# sha2017_rev1_0_1.net
KiCad netlist of a schematic drawn in EAGLE
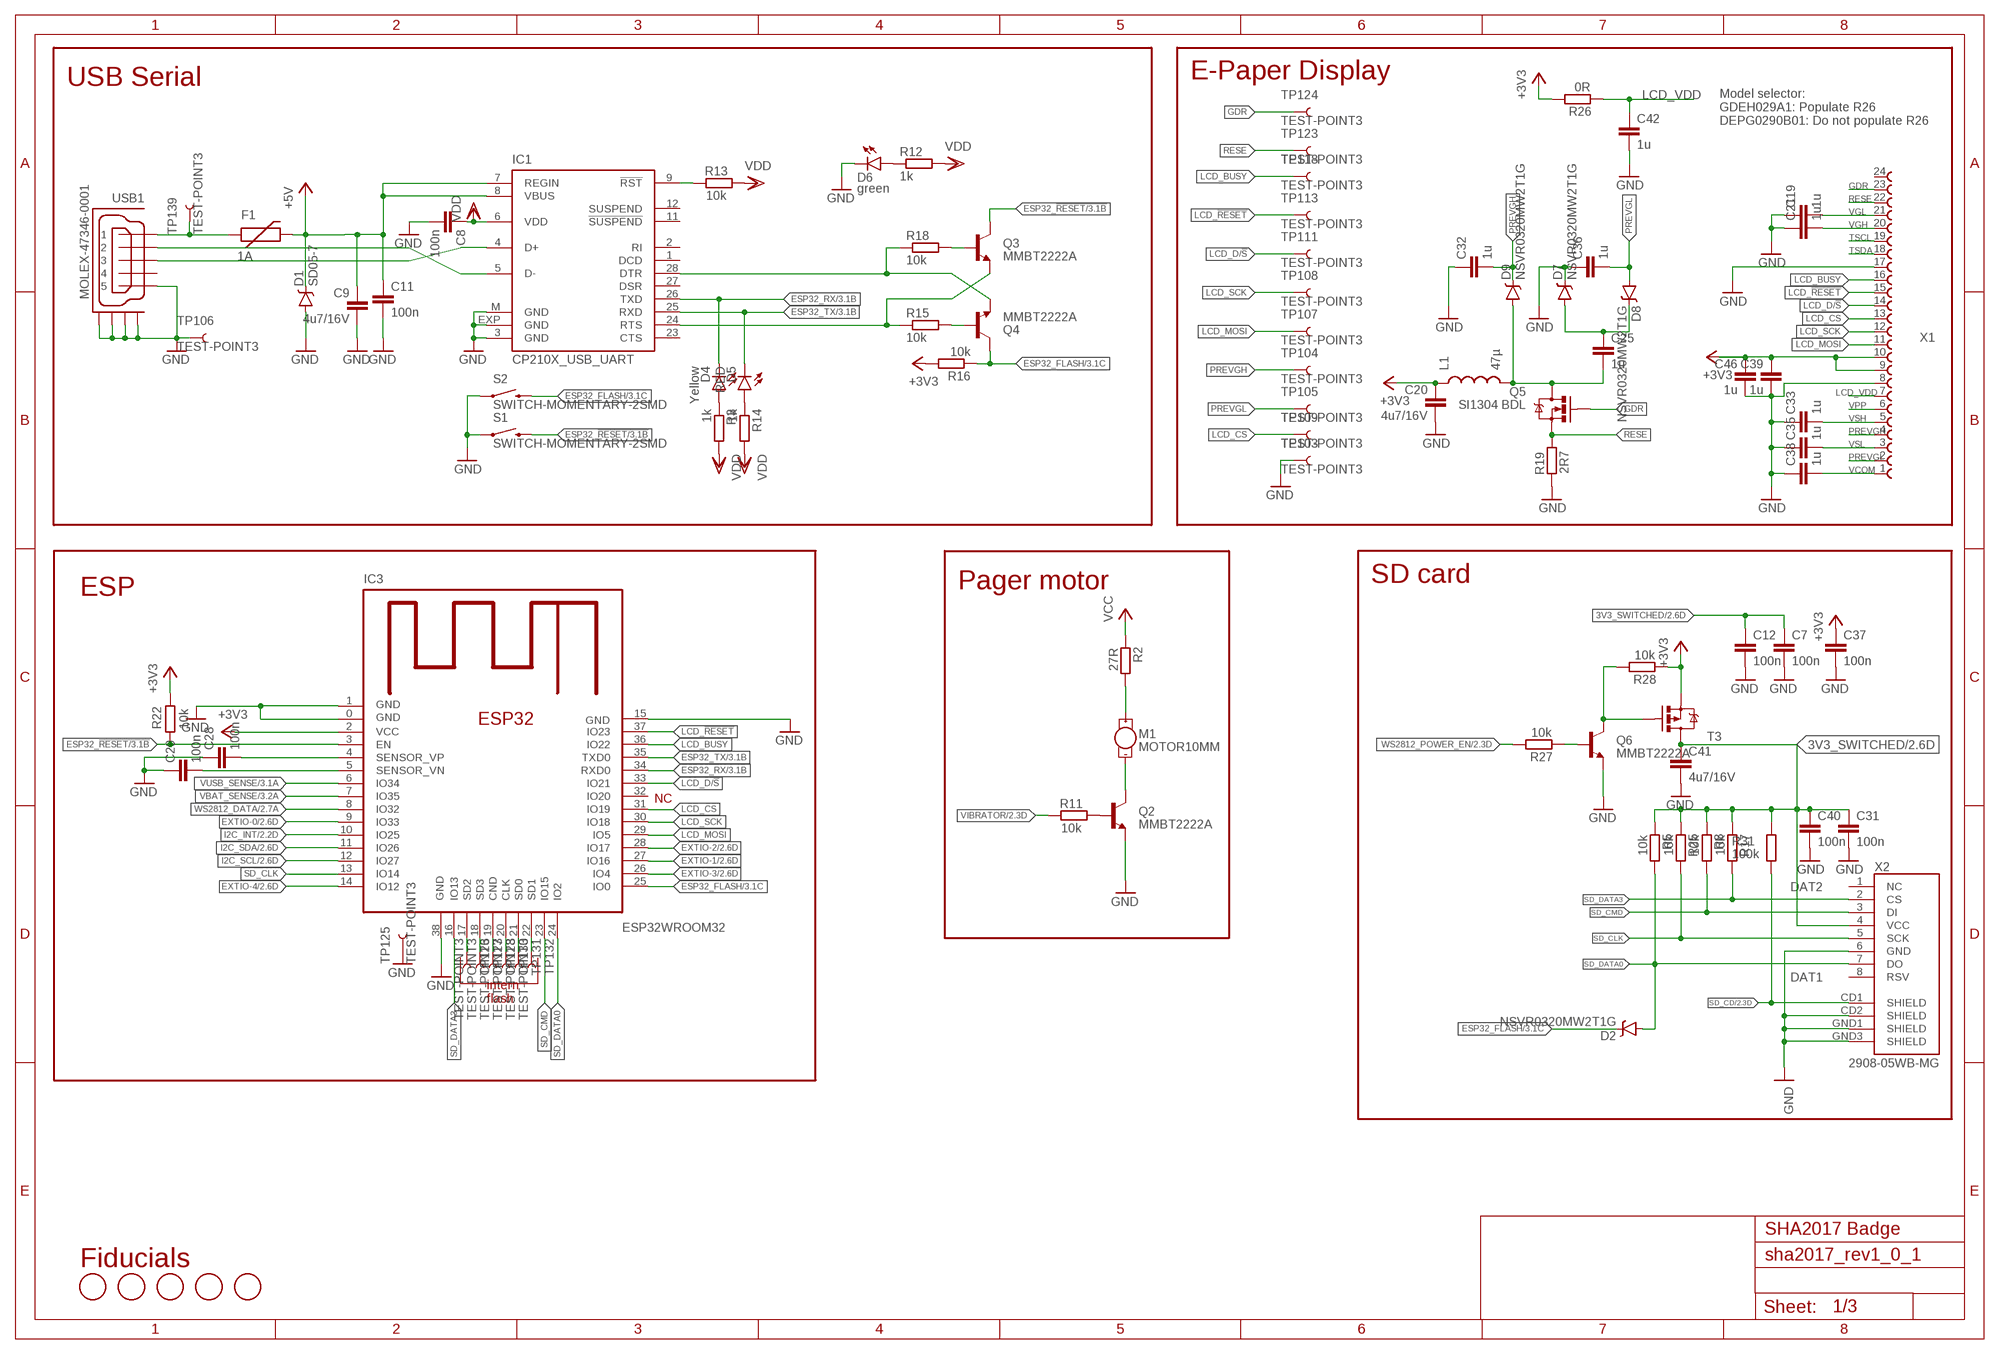
[diagram p0: schematic, sheet 1]
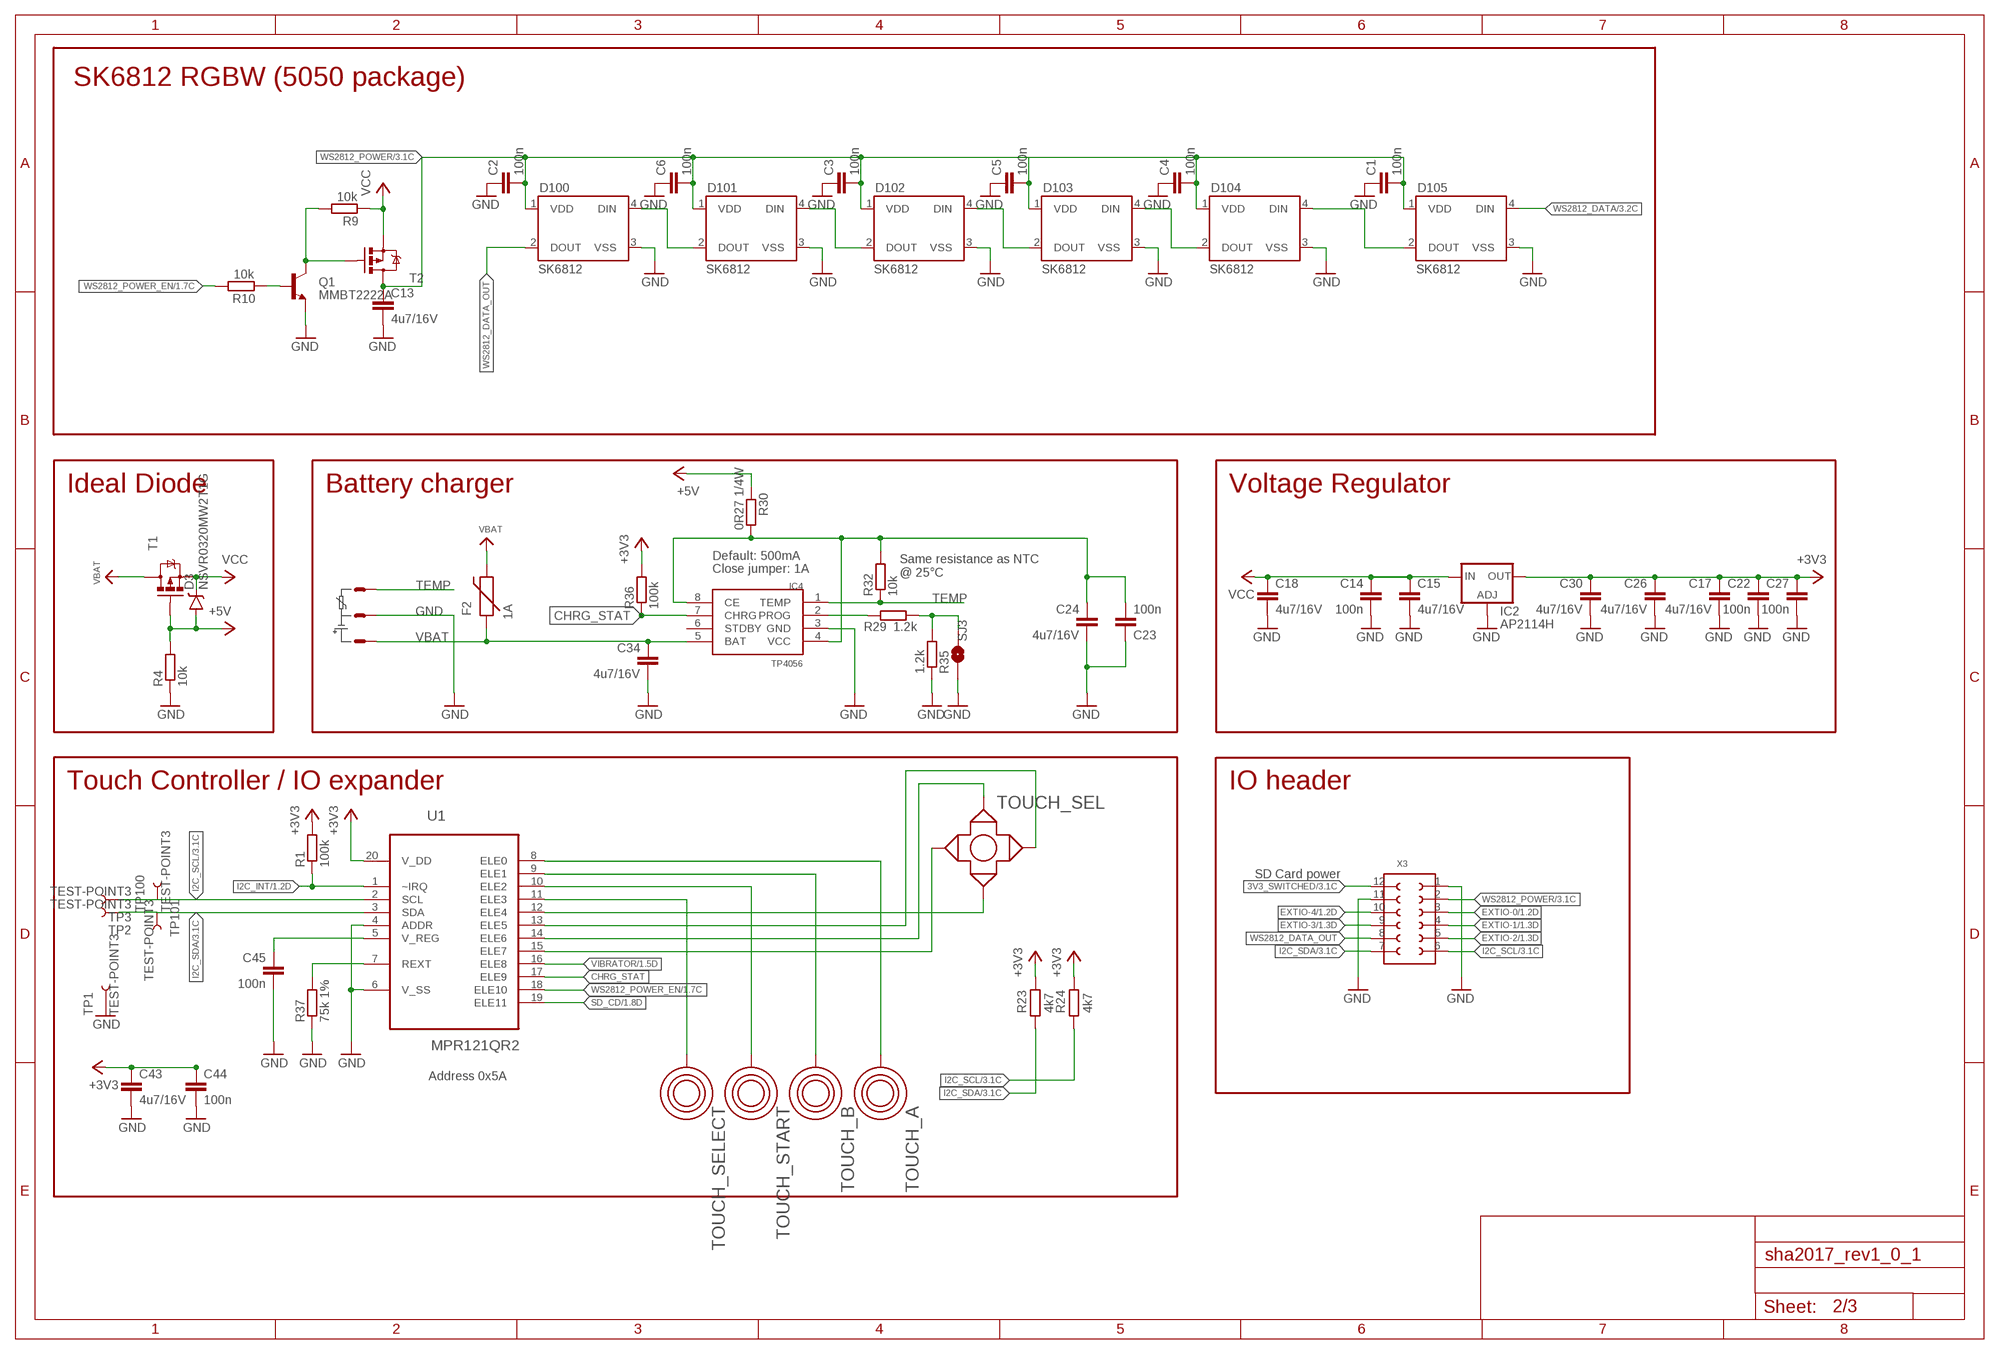
[diagram p1: schematic, sheet 2]
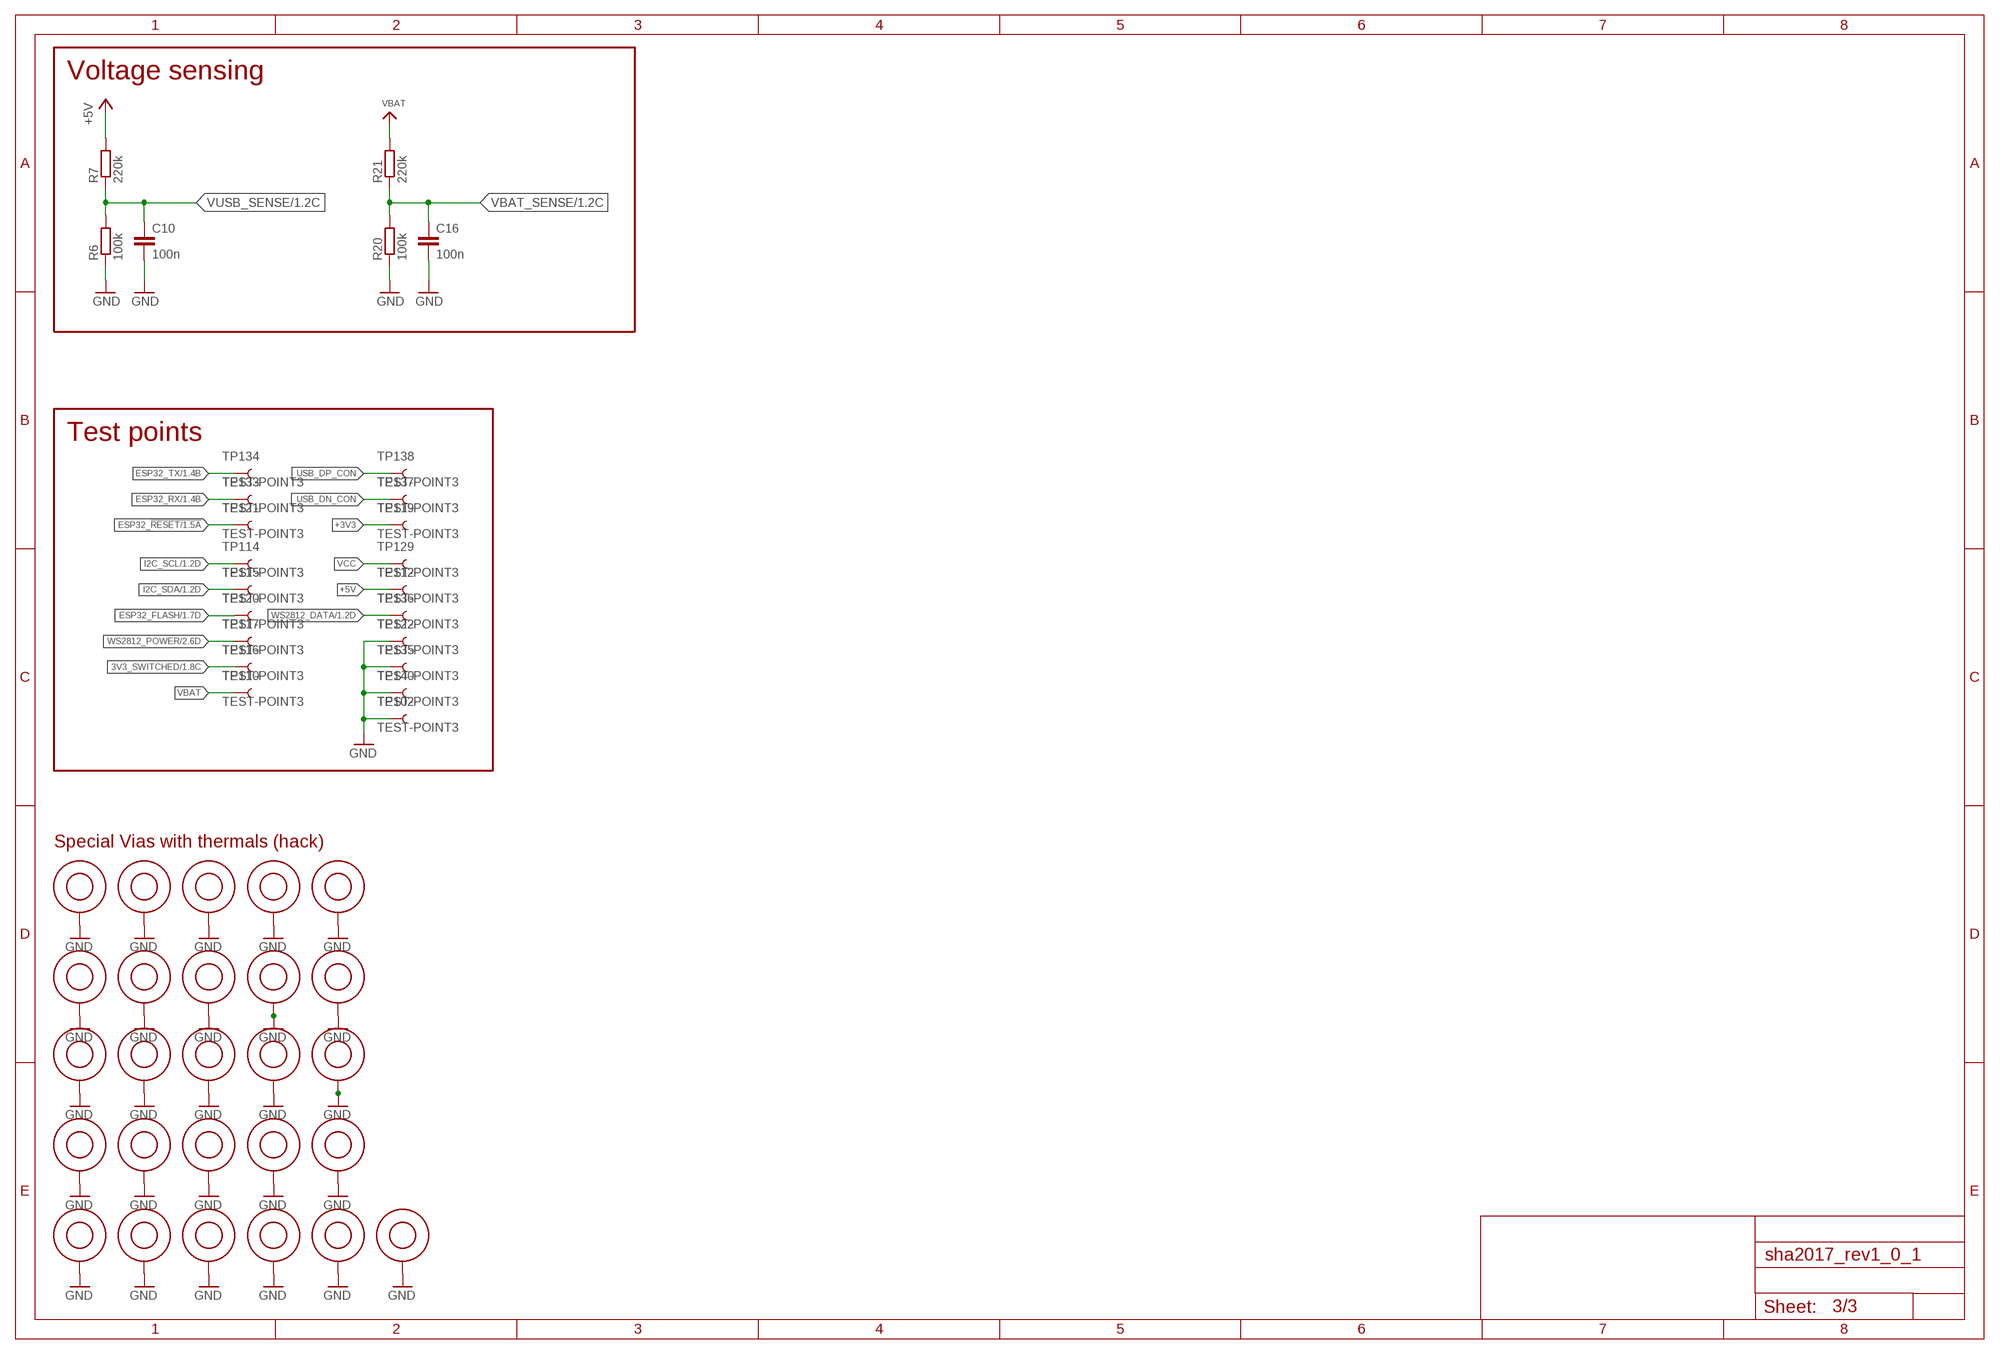
[diagram p2: schematic, sheet 3]

(export (version "E")
  (design (tool "Eeschema 10.0.6"))
  (components
    (comp (ref "C1")
      (value "100n")
      (footprint "eagle-import:C0603-DASHES")
      (fields (field (name "PARTNO") "GRM188R71H104KA93D"))
      (libsource (lib "eagle-import") (part "C0603-DASHES"))
    )
    (comp (ref "C2")
      (value "100n")
      (footprint "eagle-import:C0603-DASHES")
      (fields (field (name "PARTNO") "GRM188R71H104KA93D"))
      (libsource (lib "eagle-import") (part "C0603-DASHES"))
    )
    (comp (ref "C3")
      (value "100n")
      (footprint "eagle-import:C0603-DASHES")
      (fields (field (name "PARTNO") "GRM188R71H104KA93D"))
      (libsource (lib "eagle-import") (part "C0603-DASHES"))
    )
    (comp (ref "C4")
      (value "100n")
      (footprint "eagle-import:C0603-DASHES")
      (fields (field (name "PARTNO") "GRM188R71H104KA93D"))
      (libsource (lib "eagle-import") (part "C0603-DASHES"))
    )
    (comp (ref "C5")
      (value "100n")
      (footprint "eagle-import:C0603-DASHES")
      (fields (field (name "PARTNO") "GRM188R71H104KA93D"))
      (libsource (lib "eagle-import") (part "C0603-DASHES"))
    )
    (comp (ref "C6")
      (value "100n")
      (footprint "eagle-import:C0603-DASHES")
      (fields (field (name "PARTNO") "GRM188R71H104KA93D"))
      (libsource (lib "eagle-import") (part "C0603-DASHES"))
    )
    (comp (ref "C13")
      (value "4u7/16V")
      (footprint "eagle-import:C0805")
      (fields (field (name "PARTNO") "GRM21BR61C475KA88K"))
      (libsource (lib "eagle-import") (part "C-EUC0805"))
    )
    (comp (ref "C14")
      (value "100n")
      (footprint "eagle-import:C0603-DASHES")
      (fields (field (name "PARTNO") "GRM188R71H104KA93D"))
      (libsource (lib "eagle-import") (part "C0603-DASHES"))
    )
    (comp (ref "C15")
      (value "4u7/16V")
      (footprint "eagle-import:C0805")
      (fields (field (name "PARTNO") "GRM21BR61C475KA88K"))
      (libsource (lib "eagle-import") (part "C-EUC0805"))
    )
    (comp (ref "C17")
      (value "4u7/16V")
      (footprint "eagle-import:C0805")
      (fields (field (name "PARTNO") "GRM21BR61C475KA88K"))
      (libsource (lib "eagle-import") (part "C-EUC0805"))
    )
    (comp (ref "C18")
      (value "4u7/16V")
      (footprint "eagle-import:C0805")
      (fields (field (name "PARTNO") "GRM21BR61C475KA88K"))
      (libsource (lib "eagle-import") (part "C-EUC0805"))
    )
    (comp (ref "C22")
      (value "100n")
      (footprint "eagle-import:C0603-DASHES")
      (fields (field (name "PARTNO") "GRM188R71H104KA93D"))
      (libsource (lib "eagle-import") (part "C0603-DASHES"))
    )
    (comp (ref "C23")
      (value "100n")
      (footprint "eagle-import:C0603-DASHES")
      (fields (field (name "PARTNO") "GRM188R71H104KA93D"))
      (libsource (lib "eagle-import") (part "C0603-DASHES"))
    )
    (comp (ref "C24")
      (value "4u7/16V")
      (footprint "eagle-import:C0805")
      (fields (field (name "PARTNO") "GRM21BR61C475KA88K"))
      (libsource (lib "eagle-import") (part "C-EUC0805"))
    )
    (comp (ref "C26")
      (value "4u7/16V")
      (footprint "eagle-import:C0805")
      (fields (field (name "PARTNO") "GRM21BR61C475KA88K"))
      (libsource (lib "eagle-import") (part "C-EUC0805"))
    )
    (comp (ref "C27")
      (value "100n")
      (footprint "eagle-import:C0603-DASHES")
      (fields (field (name "PARTNO") "GRM188R71H104KA93D"))
      (libsource (lib "eagle-import") (part "C0603-DASHES"))
    )
    (comp (ref "C30")
      (value "4u7/16V")
      (footprint "eagle-import:C0805")
      (fields (field (name "PARTNO") "GRM21BR61C475KA88K"))
      (libsource (lib "eagle-import") (part "C-EUC0805"))
    )
    (comp (ref "C34")
      (value "4u7/16V")
      (footprint "eagle-import:C0805")
      (fields (field (name "PARTNO") "GRM21BR61C475KA88K"))
      (libsource (lib "eagle-import") (part "C-EUC0805"))
    )
    (comp (ref "C43")
      (value "4u7/16V")
      (footprint "eagle-import:C0805")
      (fields (field (name "PARTNO") "GRM21BR61C475KA88K"))
      (libsource (lib "eagle-import") (part "C-EUC0805"))
    )
    (comp (ref "C44")
      (value "100n")
      (footprint "eagle-import:C0603-DASHES")
      (fields (field (name "PARTNO") "GRM188R71H104KA93D"))
      (libsource (lib "eagle-import") (part "C0603-DASHES"))
    )
    (comp (ref "C45")
      (value "100n")
      (footprint "eagle-import:C0603-DASHES")
      (fields (field (name "PARTNO") "GRM188R71H104KA93D"))
      (libsource (lib "eagle-import") (part "C0603-DASHES"))
    )
    (comp (ref "D3")
      (value "NSVR0320MW2T1G")
      (footprint "eagle-import:SOD-323")
      (fields (field (name "PARTNO") "BAT20JFILM"))
      (libsource (lib "eagle-import") (part "BAT20JFILM"))
    )
    (comp (ref "D100")
      (value "SK6812")
      (footprint "eagle-import:WS2812B")
      (libsource (lib "eagle-import") (part "WS2812B"))
    )
    (comp (ref "D101")
      (value "SK6812")
      (footprint "eagle-import:WS2812B")
      (libsource (lib "eagle-import") (part "WS2812B"))
    )
    (comp (ref "D102")
      (value "SK6812")
      (footprint "eagle-import:WS2812B")
      (libsource (lib "eagle-import") (part "WS2812B"))
    )
    (comp (ref "D103")
      (value "SK6812")
      (footprint "eagle-import:WS2812B")
      (libsource (lib "eagle-import") (part "WS2812B"))
    )
    (comp (ref "D104")
      (value "SK6812")
      (footprint "eagle-import:WS2812B")
      (libsource (lib "eagle-import") (part "WS2812B"))
    )
    (comp (ref "D105")
      (value "SK6812")
      (footprint "eagle-import:WS2812B")
      (libsource (lib "eagle-import") (part "WS2812B"))
    )
    (comp (ref "F2")
      (value "1A")
      (footprint "eagle-import:PTC-1206")
      (libsource (lib "eagle-import") (part "PTCSMD"))
    )
    (comp (ref "IC2")
      (value "AP2114H")
      (footprint "eagle-import:SOT223")
      (fields (field (name "PARTNO") "AP7215-33YG-13"))
      (libsource (lib "eagle-import") (part "LD117A?S33TR"))
    )
    (comp (ref "IC4")
      (value "TP4056")
      (footprint "eagle-import:SOP-8")
      (libsource (lib "eagle-import") (part "TP4056"))
    )
    (comp (ref "Q1")
      (value "MMBT2222A")
      (footprint "eagle-import:SOT23-3")
      (fields (field (name "PARTNO") "BC817-25,215"))
      (libsource (lib "eagle-import") (part "TRANSISTOR_NPNMMBT2222A"))
    )
    (comp (ref "R1")
      (value "100k")
      (footprint "eagle-import:R0603-DASHES")
      (fields (field (name "PARTNO") "ERJ-3GEYJ104V"))
      (libsource (lib "eagle-import") (part "sha2017_rev0_1_0_dev_R0603-DASHES"))
    )
    (comp (ref "R4")
      (value "10k")
      (footprint "eagle-import:R0603-DASHES")
      (fields (field (name "PARTNO") "ERJ-3GEYJ103V"))
      (libsource (lib "eagle-import") (part "sha2017_rev0_1_0_dev_R0603-DASHES"))
    )
    (comp (ref "R9")
      (value "10k")
      (footprint "eagle-import:R0603-DASHES")
      (fields (field (name "PARTNO") "ERJ-3GEYJ103V"))
      (libsource (lib "eagle-import") (part "R0603-DASHES"))
    )
    (comp (ref "R10")
      (value "10k")
      (footprint "eagle-import:R0603-DASHES")
      (fields (field (name "PARTNO") "ERJ-3GEYJ103V"))
      (libsource (lib "eagle-import") (part "R0603-DASHES"))
    )
    (comp (ref "R23")
      (value "4k7")
      (footprint "eagle-import:R0603-DASHES")
      (fields (field (name "PARTNO") "ERJ-3GEYJ103V"))
      (libsource (lib "eagle-import") (part "sha2017_rev0_1_0_dev_R0603-DASHES"))
    )
    (comp (ref "R24")
      (value "4k7")
      (footprint "eagle-import:R0603-DASHES")
      (fields (field (name "PARTNO") "ERJ-3GEYJ103V"))
      (libsource (lib "eagle-import") (part "sha2017_rev0_1_0_dev_R0603-DASHES"))
    )
    (comp (ref "R29")
      (value "1.2k")
      (footprint "eagle-import:R0603-DASHES")
      (fields (field (name "PARTNO") "ERJ-3GEYJ222V"))
      (libsource (lib "eagle-import") (part "sha2017_rev0_1_0_dev_R0603-DASHES"))
    )
    (comp (ref "R30")
      (value "0R27 1/4W")
      (footprint "eagle-import:R1206")
      (fields (field (name "PARTNO") "ERJ-3GEYJ154V"))
      (libsource (lib "eagle-import") (part "R-EU_R1206"))
    )
    (comp (ref "R32")
      (value "10k")
      (footprint "eagle-import:R0603-DASHES")
      (fields (field (name "PARTNO") "ERJ-3GEYJ154V"))
      (libsource (lib "eagle-import") (part "sha2017_rev0_1_0_dev_R0603-DASHES"))
    )
    (comp (ref "R35")
      (value "1.2k")
      (footprint "eagle-import:R0603-DASHES")
      (fields (field (name "PARTNO") "ERJ-3GEYJ222V"))
      (libsource (lib "eagle-import") (part "sha2017_rev0_1_0_dev_R0603-DASHES"))
    )
    (comp (ref "R36")
      (value "100k")
      (footprint "eagle-import:R0603-DASHES")
      (fields (field (name "PARTNO") "ERJ-3GEYJ104V"))
      (libsource (lib "eagle-import") (part "sha2017_rev0_1_0_dev_R0603-DASHES"))
    )
    (comp (ref "R37")
      (value "75k 1%")
      (footprint "eagle-import:R0603-DASHES")
      (fields (field (name "PARTNO") "ERJ-3GEYJ104V"))
      (libsource (lib "eagle-import") (part "sha2017_rev0_1_0_dev_R0603-DASHES"))
    )
    (comp (ref "SJ3")
      (value "JUMPER-PAD-2-NOYES_SILK")
      (footprint "eagle-import:PAD-JUMPER-2-NO_YES_SILK")
      (fields (field (name "PARTNO") "NAP"))
      (libsource (lib "eagle-import") (part "JUMPER-PAD-2-NOYES_SILK"))
    )
    (comp (ref "T1")
      (value "MOSFET-PCHANNEL")
      (footprint "eagle-import:SOT23-3")
      (libsource (lib "eagle-import") (part "MOSFET-PCHANNEL"))
    )
    (comp (ref "T2")
      (value "MOSFET-PCHANNEL")
      (footprint "eagle-import:SOT23-3")
      (libsource (lib "eagle-import") (part "MOSFET-PCHANNEL"))
    )
    (comp (ref "TOUCH_A")
      (value "TOUCHROUND")
      (footprint "eagle-import:TOUCH_BUTTON")
      (fields (field (name "PARTNO") "NAP"))
      (libsource (lib "eagle-import") (part "TOUCHROUND"))
    )
    (comp (ref "TOUCH_B")
      (value "TOUCHROUND")
      (footprint "eagle-import:TOUCH_BUTTON")
      (fields (field (name "PARTNO") "NAP"))
      (libsource (lib "eagle-import") (part "TOUCHROUND"))
    )
    (comp (ref "TOUCH_SEL")
      (value "TOUCH_CROSS")
      (footprint "eagle-import:TOUCH_CROSS")
      (fields (field (name "PARTNO") "NAP"))
      (libsource (lib "eagle-import") (part "TOUCH_CROSS"))
    )
    (comp (ref "TOUCH_SELECT")
      (value "TOUCHSELECT")
      (footprint "eagle-import:TOUCH_SELECT")
      (libsource (lib "eagle-import") (part "TOUCHSELECT"))
    )
    (comp (ref "TOUCH_START")
      (value "TOUCHSELECT")
      (footprint "eagle-import:TOUCH_SELECT")
      (libsource (lib "eagle-import") (part "TOUCHSELECT"))
    )
    (comp (ref "TP1")
      (value "TEST-POINT3")
      (footprint "eagle-import:PAD.03X.03")
      (fields (field (name "PARTNO") "NAP"))
      (libsource (lib "eagle-import") (part "TEST-POINT3"))
    )
    (comp (ref "TP2")
      (value "TEST-POINT3")
      (footprint "eagle-import:PAD.03X.03")
      (fields (field (name "PARTNO") "NAP"))
      (libsource (lib "eagle-import") (part "TEST-POINT3"))
    )
    (comp (ref "TP3")
      (value "TEST-POINT3")
      (footprint "eagle-import:PAD.03X.03")
      (fields (field (name "PARTNO") "NAP"))
      (libsource (lib "eagle-import") (part "TEST-POINT3"))
    )
    (comp (ref "TP100")
      (value "TEST-POINT3")
      (footprint "eagle-import:PAD.03X.03")
      (fields (field (name "PARTNO") "NAP"))
      (libsource (lib "eagle-import") (part "TEST-POINT3"))
    )
    (comp (ref "TP101")
      (value "TEST-POINT3")
      (footprint "eagle-import:PAD.03X.03")
      (fields (field (name "PARTNO") "NAP"))
      (libsource (lib "eagle-import") (part "TEST-POINT3"))
    )
    (comp (ref "U1")
      (value "MPR121QR2")
      (footprint "eagle-import:QFN40P300X300X60-20N")
      (libsource (lib "eagle-import") (part "MPR121QR2"))
    )
    (comp (ref "X3")
      (value "610X12243021")
      (footprint "eagle-import:610X12243021")
      (fields (field (name "PARTNO") "517-153208-2020-TB"))
      (libsource (lib "eagle-import") (part "610X12243021"))
    )
    (comp (ref "X4")
      (value "JST-PH3")
      (footprint "eagle-import:JST-PH3")
      (libsource (lib "eagle-import") (part "JST-PH3"))
    )
    (comp (ref "$$U$1")
      (value "VIA")
      (footprint "eagle-import:VIA")
      (fields (field (name "PARTNO") "NAP"))
      (libsource (lib "eagle-import") (part "VIA"))
    )
    (comp (ref "$$U$2")
      (value "VIA")
      (footprint "eagle-import:VIA")
      (fields (field (name "PARTNO") "NAP"))
      (libsource (lib "eagle-import") (part "VIA"))
    )
    (comp (ref "$$U$3")
      (value "VIA")
      (footprint "eagle-import:VIA")
      (fields (field (name "PARTNO") "NAP"))
      (libsource (lib "eagle-import") (part "VIA"))
    )
    (comp (ref "$$U$4")
      (value "VIA")
      (footprint "eagle-import:VIA")
      (fields (field (name "PARTNO") "NAP"))
      (libsource (lib "eagle-import") (part "VIA"))
    )
    (comp (ref "$$U$5")
      (value "VIA")
      (footprint "eagle-import:VIA")
      (fields (field (name "PARTNO") "NAP"))
      (libsource (lib "eagle-import") (part "VIA"))
    )
    (comp (ref "$$U$6")
      (value "VIA")
      (footprint "eagle-import:VIA")
      (fields (field (name "PARTNO") "NAP"))
      (libsource (lib "eagle-import") (part "VIA"))
    )
    (comp (ref "$$U$7")
      (value "VIA")
      (footprint "eagle-import:VIA")
      (fields (field (name "PARTNO") "NAP"))
      (libsource (lib "eagle-import") (part "VIA"))
    )
    (comp (ref "$$U$8")
      (value "VIA")
      (footprint "eagle-import:VIA")
      (fields (field (name "PARTNO") "NAP"))
      (libsource (lib "eagle-import") (part "VIA"))
    )
    (comp (ref "$$U$9")
      (value "VIA")
      (footprint "eagle-import:VIA")
      (fields (field (name "PARTNO") "NAP"))
      (libsource (lib "eagle-import") (part "VIA"))
    )
    (comp (ref "C10")
      (value "100n")
      (footprint "eagle-import:C0603-DASHES")
      (fields (field (name "PARTNO") "GRM188R71H104KA93D"))
      (libsource (lib "eagle-import") (part "C0603-DASHES"))
    )
    (comp (ref "C16")
      (value "100n")
      (footprint "eagle-import:C0603-DASHES")
      (fields (field (name "PARTNO") "GRM188R71H104KA93D"))
      (libsource (lib "eagle-import") (part "C0603-DASHES"))
    )
    (comp (ref "R6")
      (value "100k")
      (footprint "eagle-import:R0603-DASHES")
      (fields (field (name "PARTNO") "ERJ-3GEYJ104V"))
      (libsource (lib "eagle-import") (part "sha2017_rev0_1_0_dev_R0603-DASHES"))
    )
    (comp (ref "R7")
      (value "220k")
      (footprint "eagle-import:R0603-DASHES")
      (fields (field (name "PARTNO") "ERJ-3GEYJ224V"))
      (libsource (lib "eagle-import") (part "sha2017_rev0_1_0_dev_R0603-DASHES"))
    )
    (comp (ref "R20")
      (value "100k")
      (footprint "eagle-import:R0603-DASHES")
      (fields (field (name "PARTNO") "ERJ-3GEYJ104V"))
      (libsource (lib "eagle-import") (part "sha2017_rev0_1_0_dev_R0603-DASHES"))
    )
    (comp (ref "R21")
      (value "220k")
      (footprint "eagle-import:R0603-DASHES")
      (fields (field (name "PARTNO") "ERJ-3GEYJ224V"))
      (libsource (lib "eagle-import") (part "sha2017_rev0_1_0_dev_R0603-DASHES"))
    )
    (comp (ref "TP102")
      (value "TEST-POINT3")
      (footprint "eagle-import:PAD.03X.03")
      (fields (field (name "PARTNO") "NAP"))
      (libsource (lib "eagle-import") (part "TEST-POINT3"))
    )
    (comp (ref "TP110")
      (value "TEST-POINT3")
      (footprint "eagle-import:PAD.03X.03")
      (fields (field (name "PARTNO") "NAP"))
      (libsource (lib "eagle-import") (part "TEST-POINT3"))
    )
    (comp (ref "TP112")
      (value "TEST-POINT3")
      (footprint "eagle-import:PAD.03X.03")
      (fields (field (name "PARTNO") "NAP"))
      (libsource (lib "eagle-import") (part "TEST-POINT3"))
    )
    (comp (ref "TP114")
      (value "TEST-POINT3")
      (footprint "eagle-import:PAD.03X.03")
      (fields (field (name "PARTNO") "NAP"))
      (libsource (lib "eagle-import") (part "TEST-POINT3"))
    )
    (comp (ref "TP115")
      (value "TEST-POINT3")
      (footprint "eagle-import:PAD.03X.03")
      (fields (field (name "PARTNO") "NAP"))
      (libsource (lib "eagle-import") (part "TEST-POINT3"))
    )
    (comp (ref "TP116")
      (value "TEST-POINT3")
      (footprint "eagle-import:PAD.03X.03")
      (fields (field (name "PARTNO") "NAP"))
      (libsource (lib "eagle-import") (part "TEST-POINT3"))
    )
    (comp (ref "TP117")
      (value "TEST-POINT3")
      (footprint "eagle-import:PAD.03X.03")
      (fields (field (name "PARTNO") "NAP"))
      (libsource (lib "eagle-import") (part "TEST-POINT3"))
    )
    (comp (ref "TP119")
      (value "TEST-POINT3")
      (footprint "eagle-import:PAD.03X.03")
      (fields (field (name "PARTNO") "NAP"))
      (libsource (lib "eagle-import") (part "TEST-POINT3"))
    )
    (comp (ref "TP120")
      (value "TEST-POINT3")
      (footprint "eagle-import:PAD.03X.03")
      (fields (field (name "PARTNO") "NAP"))
      (libsource (lib "eagle-import") (part "TEST-POINT3"))
    )
    (comp (ref "TP121")
      (value "TEST-POINT3")
      (footprint "eagle-import:PAD.03X.03")
      (fields (field (name "PARTNO") "NAP"))
      (libsource (lib "eagle-import") (part "TEST-POINT3"))
    )
    (comp (ref "TP122")
      (value "TEST-POINT3")
      (footprint "eagle-import:PAD.03X.03")
      (fields (field (name "PARTNO") "NAP"))
      (libsource (lib "eagle-import") (part "TEST-POINT3"))
    )
    (comp (ref "TP129")
      (value "TEST-POINT3")
      (footprint "eagle-import:PAD.03X.03")
      (fields (field (name "PARTNO") "NAP"))
      (libsource (lib "eagle-import") (part "TEST-POINT3"))
    )
    (comp (ref "TP133")
      (value "TEST-POINT3")
      (footprint "eagle-import:PAD.03X.03")
      (fields (field (name "PARTNO") "NAP"))
      (libsource (lib "eagle-import") (part "TEST-POINT3"))
    )
    (comp (ref "TP134")
      (value "TEST-POINT3")
      (footprint "eagle-import:PAD.03X.03")
      (fields (field (name "PARTNO") "NAP"))
      (libsource (lib "eagle-import") (part "TEST-POINT3"))
    )
    (comp (ref "TP135")
      (value "TEST-POINT3")
      (footprint "eagle-import:PAD.03X.03")
      (fields (field (name "PARTNO") "NAP"))
      (libsource (lib "eagle-import") (part "TEST-POINT3"))
    )
    (comp (ref "TP136")
      (value "TEST-POINT3")
      (footprint "eagle-import:PAD.03X.03")
      (fields (field (name "PARTNO") "NAP"))
      (libsource (lib "eagle-import") (part "TEST-POINT3"))
    )
    (comp (ref "TP137")
      (value "TEST-POINT3")
      (footprint "eagle-import:PAD.03X.03")
      (fields (field (name "PARTNO") "NAP"))
      (libsource (lib "eagle-import") (part "TEST-POINT3"))
    )
    (comp (ref "TP138")
      (value "TEST-POINT3")
      (footprint "eagle-import:PAD.03X.03")
      (fields (field (name "PARTNO") "NAP"))
      (libsource (lib "eagle-import") (part "TEST-POINT3"))
    )
    (comp (ref "TP140")
      (value "TEST-POINT3")
      (footprint "eagle-import:PAD.03X.03")
      (fields (field (name "PARTNO") "NAP"))
      (libsource (lib "eagle-import") (part "TEST-POINT3"))
    )
    (comp (ref "U$2")
      (value "VIA")
      (footprint "eagle-import:VIA")
      (fields (field (name "PARTNO") "NAP"))
      (libsource (lib "eagle-import") (part "VIA"))
    )
    (comp (ref "U$3")
      (value "VIA")
      (footprint "eagle-import:VIA")
      (fields (field (name "PARTNO") "NAP"))
      (libsource (lib "eagle-import") (part "VIA"))
    )
    (comp (ref "U$4")
      (value "VIA")
      (footprint "eagle-import:VIA")
      (fields (field (name "PARTNO") "NAP"))
      (libsource (lib "eagle-import") (part "VIA"))
    )
    (comp (ref "U$5")
      (value "VIA")
      (footprint "eagle-import:VIA")
      (fields (field (name "PARTNO") "NAP"))
      (libsource (lib "eagle-import") (part "VIA"))
    )
    (comp (ref "U$6")
      (value "VIA")
      (footprint "eagle-import:VIA")
      (fields (field (name "PARTNO") "NAP"))
      (libsource (lib "eagle-import") (part "VIA"))
    )
    (comp (ref "U$10")
      (value "VIA")
      (footprint "eagle-import:VIA")
      (fields (field (name "PARTNO") "NAP"))
      (libsource (lib "eagle-import") (part "VIA"))
    )
    (comp (ref "U$11")
      (value "VIA")
      (footprint "eagle-import:VIA")
      (fields (field (name "PARTNO") "NAP"))
      (libsource (lib "eagle-import") (part "VIA"))
    )
    (comp (ref "U$12")
      (value "VIA")
      (footprint "eagle-import:VIA")
      (fields (field (name "PARTNO") "NAP"))
      (libsource (lib "eagle-import") (part "VIA"))
    )
    (comp (ref "U$13")
      (value "VIA")
      (footprint "eagle-import:VIA")
      (fields (field (name "PARTNO") "NAP"))
      (libsource (lib "eagle-import") (part "VIA"))
    )
    (comp (ref "U$14")
      (value "VIA")
      (footprint "eagle-import:VIA")
      (fields (field (name "PARTNO") "NAP"))
      (libsource (lib "eagle-import") (part "VIA"))
    )
    (comp (ref "U$15")
      (value "VIA")
      (footprint "eagle-import:VIA")
      (fields (field (name "PARTNO") "NAP"))
      (libsource (lib "eagle-import") (part "VIA"))
    )
    (comp (ref "U$16")
      (value "VIA")
      (footprint "eagle-import:VIA")
      (fields (field (name "PARTNO") "NAP"))
      (libsource (lib "eagle-import") (part "VIA"))
    )
    (comp (ref "U$17")
      (value "VIA")
      (footprint "eagle-import:VIA")
      (fields (field (name "PARTNO") "NAP"))
      (libsource (lib "eagle-import") (part "VIA"))
    )
    (comp (ref "U$18")
      (value "VIA")
      (footprint "eagle-import:VIA")
      (fields (field (name "PARTNO") "NAP"))
      (libsource (lib "eagle-import") (part "VIA"))
    )
    (comp (ref "U$19")
      (value "VIA")
      (footprint "eagle-import:VIA")
      (fields (field (name "PARTNO") "NAP"))
      (libsource (lib "eagle-import") (part "VIA"))
    )
    (comp (ref "U$20")
      (value "VIA")
      (footprint "eagle-import:VIA")
      (fields (field (name "PARTNO") "NAP"))
      (libsource (lib "eagle-import") (part "VIA"))
    )
    (comp (ref "U$21")
      (value "VIA")
      (footprint "eagle-import:VIA")
      (fields (field (name "PARTNO") "NAP"))
      (libsource (lib "eagle-import") (part "VIA"))
    )
    (comp (ref "U$22")
      (value "VIA")
      (footprint "eagle-import:VIA")
      (fields (field (name "PARTNO") "NAP"))
      (libsource (lib "eagle-import") (part "VIA"))
    )
    (comp (ref "U$23")
      (value "VIA")
      (footprint "eagle-import:VIA")
      (fields (field (name "PARTNO") "NAP"))
      (libsource (lib "eagle-import") (part "VIA"))
    )
    (comp (ref "C7")
      (value "100n")
      (footprint "eagle-import:C0603-DASHES")
      (fields (field (name "PARTNO") "GRM188R71H104KA93D"))
      (libsource (lib "eagle-import") (part "C0603-DASHES"))
    )
    (comp (ref "C8")
      (value "100n")
      (footprint "eagle-import:C0603-DASHES")
      (fields (field (name "PARTNO") "GRM188R71H104KA93D"))
      (libsource (lib "eagle-import") (part "C0603-DASHES"))
    )
    (comp (ref "C9")
      (value "4u7/16V")
      (footprint "eagle-import:C0805")
      (fields (field (name "PARTNO") "GRM21BR61C475KA88K"))
      (libsource (lib "eagle-import") (part "C-EUC0805"))
    )
    (comp (ref "C11")
      (value "100n")
      (footprint "eagle-import:C0603-DASHES")
      (fields (field (name "PARTNO") "GRM188R71H104KA93D"))
      (libsource (lib "eagle-import") (part "C0603-DASHES"))
    )
    (comp (ref "C12")
      (value "100n")
      (footprint "eagle-import:C0603-DASHES")
      (fields (field (name "PARTNO") "GRM188R71H104KA93D"))
      (libsource (lib "eagle-import") (part "C0603-DASHES"))
    )
    (comp (ref "C19")
      (value "1u")
      (footprint "eagle-import:C0603-DASHES")
      (fields (field (name "PARTNO") "GRM188R61E105KA12D"))
      (libsource (lib "eagle-import") (part "C0603-DASHES"))
    )
    (comp (ref "C20")
      (value "4u7/16V")
      (footprint "eagle-import:C0805")
      (fields (field (name "PARTNO") "GRM21BR61C475KA88K"))
      (libsource (lib "eagle-import") (part "C-EUC0805"))
    )
    (comp (ref "C21")
      (value "1u")
      (footprint "eagle-import:C0603-DASHES")
      (fields (field (name "PARTNO") "GRM188R61E105KA12D"))
      (libsource (lib "eagle-import") (part "C0603-DASHES"))
    )
    (comp (ref "C25")
      (value "1u")
      (footprint "eagle-import:C0603-DASHES")
      (fields (field (name "PARTNO") "GRM188R61E105KA12D"))
      (libsource (lib "eagle-import") (part "C0603-DASHES"))
    )
    (comp (ref "C28")
      (value "100n")
      (footprint "eagle-import:C0603-DASHES")
      (fields (field (name "PARTNO") "GRM188R71H104KA93D"))
      (libsource (lib "eagle-import") (part "C0603-DASHES"))
    )
    (comp (ref "C29")
      (value "100n")
      (footprint "eagle-import:C0603-DASHES")
      (fields (field (name "PARTNO") "GRM188R71H104KA93D"))
      (libsource (lib "eagle-import") (part "C0603-DASHES"))
    )
    (comp (ref "C31")
      (value "100n")
      (footprint "eagle-import:C0603-DASHES")
      (fields (field (name "PARTNO") "GRM188R71H104KA93D"))
      (libsource (lib "eagle-import") (part "C0603-DASHES"))
    )
    (comp (ref "C32")
      (value "1u")
      (footprint "eagle-import:C0603-DASHES")
      (fields (field (name "PARTNO") "GRM188R61E105KA12D"))
      (libsource (lib "eagle-import") (part "C0603-DASHES"))
    )
    (comp (ref "C33")
      (value "1u")
      (footprint "eagle-import:C0603-DASHES")
      (fields (field (name "PARTNO") "GRM188R61E105KA12D"))
      (libsource (lib "eagle-import") (part "C0603-DASHES"))
    )
    (comp (ref "C35")
      (value "1u")
      (footprint "eagle-import:C0603-DASHES")
      (fields (field (name "PARTNO") "GRM188R61E105KA12D"))
      (libsource (lib "eagle-import") (part "C0603-DASHES"))
    )
    (comp (ref "C36")
      (value "1u")
      (footprint "eagle-import:C0603-DASHES")
      (fields (field (name "PARTNO") "GRM188R61E105KA12D"))
      (libsource (lib "eagle-import") (part "C0603-DASHES"))
    )
    (comp (ref "C37")
      (value "100n")
      (footprint "eagle-import:C0603-DASHES")
      (fields (field (name "PARTNO") "GRM188R71H104KA93D"))
      (libsource (lib "eagle-import") (part "C0603-DASHES"))
    )
    (comp (ref "C38")
      (value "1u")
      (footprint "eagle-import:C0603-DASHES")
      (fields (field (name "PARTNO") "GRM188R61E105KA12D"))
      (libsource (lib "eagle-import") (part "C0603-DASHES"))
    )
    (comp (ref "C39")
      (value "1u")
      (footprint "eagle-import:C0603-DASHES")
      (fields (field (name "PARTNO") "GRM188R61E105KA12D"))
      (libsource (lib "eagle-import") (part "C0603-DASHES"))
    )
    (comp (ref "C40")
      (value "100n")
      (footprint "eagle-import:C0603-DASHES")
      (fields (field (name "PARTNO") "GRM188R71H104KA93D"))
      (libsource (lib "eagle-import") (part "C0603-DASHES"))
    )
    (comp (ref "C41")
      (value "4u7/16V")
      (footprint "eagle-import:C0805")
      (fields (field (name "PARTNO") "GRM21BR61C475KA88K"))
      (libsource (lib "eagle-import") (part "C-EUC0805"))
    )
    (comp (ref "C42")
      (value "1u")
      (footprint "eagle-import:C0603-DASHES")
      (fields (field (name "PARTNO") "GRM188R61E105KA12D"))
      (libsource (lib "eagle-import") (part "C0603-DASHES"))
    )
    (comp (ref "C46")
      (value "1u")
      (footprint "eagle-import:C0603-DASHES")
      (fields (field (name "PARTNO") "GRM188R61E105KA12D"))
      (libsource (lib "eagle-import") (part "C0603-DASHES"))
    )
    (comp (ref "D1")
      (value "SD05-7")
      (footprint "eagle-import:SOD-323")
      (libsource (lib "eagle-import") (part "DIODE-SCHOTTKY-PMEG4005EJ"))
    )
    (comp (ref "D2")
      (value "NSVR0320MW2T1G")
      (footprint "eagle-import:SOD-323")
      (fields (field (name "PARTNO") "BAT20JFILM"))
      (libsource (lib "eagle-import") (part "BAT20JFILM"))
    )
    (comp (ref "D4")
      (value "Yellow")
      (footprint "eagle-import:LED-0603")
      (libsource (lib "eagle-import") (part "LED0603"))
    )
    (comp (ref "D5")
      (value "RED")
      (footprint "eagle-import:LED-0603")
      (libsource (lib "eagle-import") (part "LED0603"))
    )
    (comp (ref "D6")
      (value "green")
      (footprint "eagle-import:LED-0603")
      (libsource (lib "eagle-import") (part "LED0603"))
    )
    (comp (ref "D7")
      (value "NSVR0320MW2T1G")
      (footprint "eagle-import:SOD-323")
      (fields (field (name "PARTNO") "BAT20JFILM"))
      (libsource (lib "eagle-import") (part "BAT20JFILM"))
    )
    (comp (ref "D8")
      (value "NSVR0320MW2T1G")
      (footprint "eagle-import:SOD-323")
      (fields (field (name "PARTNO") "BAT20JFILM"))
      (libsource (lib "eagle-import") (part "BAT20JFILM"))
    )
    (comp (ref "D9")
      (value "NSVR0320MW2T1G")
      (footprint "eagle-import:SOD-323")
      (fields (field (name "PARTNO") "BAT20JFILM"))
      (libsource (lib "eagle-import") (part "BAT20JFILM"))
    )
    (comp (ref "F1")
      (value "1A")
      (footprint "eagle-import:PTC-1206")
      (libsource (lib "eagle-import") (part "PTCSMD"))
    )
    (comp (ref "FD1")
      (value "FIDUCIAL")
      (footprint "eagle-import:FIDUCIAL_1MM")
      (fields (field (name "PARTNO") "NAP"))
      (libsource (lib "eagle-import") (part "FIDUCIAL"))
    )
    (comp (ref "FD2")
      (value "FIDUCIAL")
      (footprint "eagle-import:FIDUCIAL_1MM")
      (fields (field (name "PARTNO") "NAP"))
      (libsource (lib "eagle-import") (part "FIDUCIAL"))
    )
    (comp (ref "FD3")
      (value "FIDUCIAL")
      (footprint "eagle-import:FIDUCIAL_1MM")
      (fields (field (name "PARTNO") "NAP"))
      (libsource (lib "eagle-import") (part "FIDUCIAL"))
    )
    (comp (ref "FD4")
      (value "FIDUCIAL")
      (footprint "eagle-import:FIDUCIAL_1MM")
      (fields (field (name "PARTNO") "NAP"))
      (libsource (lib "eagle-import") (part "FIDUCIAL"))
    )
    (comp (ref "FD5")
      (value "FIDUCIAL")
      (footprint "eagle-import:FIDUCIAL_1MM")
      (fields (field (name "PARTNO") "NAP"))
      (libsource (lib "eagle-import") (part "FIDUCIAL"))
    )
    (comp (ref "IC1")
      (value "CP210X_USB_UART")
      (footprint "eagle-import:MLP28")
      (fields (field (name "PARTNO") "CP2102-GMR"))
      (libsource (lib "eagle-import") (part "CP210X_USB_UART"))
    )
    (comp (ref "IC3")
      (value "ESP32WROOM32")
      (footprint "eagle-import:ESP32MOD")
      (libsource (lib "eagle-import") (part "ESP32WROOM32"))
    )
    (comp (ref "L1")
      (value "47µ")
      (footprint "eagle-import:1210")
      (fields (field (name "PARTNO") "NLCV32T-220K-EF"))
      (libsource (lib "eagle-import") (part "INDUCTOR1210"))
    )
    (comp (ref "M1")
      (value "MOTOR10MM")
      (footprint "eagle-import:VIBE-MOTOR-10MM")
      (libsource (lib "eagle-import") (part "MOTOR10MM"))
    )
    (comp (ref "Q2")
      (value "MMBT2222A")
      (footprint "eagle-import:SOT23-3")
      (fields (field (name "PARTNO") "BC817-25,215"))
      (libsource (lib "eagle-import") (part "TRANSISTOR_NPNMMBT2222A"))
    )
    (comp (ref "Q3")
      (value "MMBT2222A")
      (footprint "eagle-import:SOT23-3")
      (fields (field (name "PARTNO") "BC817-25,215"))
      (libsource (lib "eagle-import") (part "TRANSISTOR_NPNMMBT2222A"))
    )
    (comp (ref "Q4")
      (value "MMBT2222A")
      (footprint "eagle-import:SOT23-3")
      (fields (field (name "PARTNO") "BC817-25,215"))
      (libsource (lib "eagle-import") (part "TRANSISTOR_NPNMMBT2222A"))
    )
    (comp (ref "Q5")
      (value "SI1304 BDL")
      (footprint "eagle-import:SOT323")
      (fields (field (name "PARTNO") "SI1308EDL-T1-GE3"))
      (libsource (lib "eagle-import") (part "MOSFET-NCHANNEL2N7002PW"))
    )
    (comp (ref "Q6")
      (value "MMBT2222A")
      (footprint "eagle-import:SOT23-3")
      (fields (field (name "PARTNO") "BC817-25,215"))
      (libsource (lib "eagle-import") (part "TRANSISTOR_NPNMMBT2222A"))
    )
    (comp (ref "R2")
      (value "27R")
      (footprint "eagle-import:R1206")
      (fields (field (name "PARTNO") "ERJ-3GEYJ220V"))
      (libsource (lib "eagle-import") (part "R-EU_R1206"))
    )
    (comp (ref "R3")
      (value "1k")
      (footprint "eagle-import:R0603-DASHES")
      (fields (field (name "PARTNO") "ERJ-3GEYJ102V"))
      (libsource (lib "eagle-import") (part "sha2017_rev0_1_0_dev_R0603-DASHES"))
    )
    (comp (ref "R5")
      (value "10k")
      (footprint "eagle-import:R0603-DASHES")
      (fields (field (name "PARTNO") "ERJ-3GEYJ103V"))
      (libsource (lib "eagle-import") (part "R0603-DASHES"))
    )
    (comp (ref "R8")
      (value "10k")
      (footprint "eagle-import:R0603-DASHES")
      (fields (field (name "PARTNO") "ERJ-3GEYJ103V"))
      (libsource (lib "eagle-import") (part "R0603-DASHES"))
    )
    (comp (ref "R11")
      (value "10k")
      (footprint "eagle-import:R0603-DASHES")
      (fields (field (name "PARTNO") "ERJ-3GEYJ103V"))
      (libsource (lib "eagle-import") (part "R0603-DASHES"))
    )
    (comp (ref "R12")
      (value "1k")
      (footprint "eagle-import:R0603-DASHES")
      (fields (field (name "PARTNO") "ERJ-3GEYJ102V"))
      (libsource (lib "eagle-import") (part "sha2017_rev0_1_0_dev_R0603-DASHES"))
    )
    (comp (ref "R13")
      (value "10k")
      (footprint "eagle-import:R0603-DASHES")
      (fields (field (name "PARTNO") "ERJ-3GEYJ103V"))
      (libsource (lib "eagle-import") (part "sha2017_rev0_1_0_dev_R0603-DASHES"))
    )
    (comp (ref "R14")
      (value "1k")
      (footprint "eagle-import:R0603-DASHES")
      (fields (field (name "PARTNO") "ERJ-3GEYJ102V"))
      (libsource (lib "eagle-import") (part "sha2017_rev0_1_0_dev_R0603-DASHES"))
    )
    (comp (ref "R15")
      (value "10k")
      (footprint "eagle-import:R0603-DASHES")
      (fields (field (name "PARTNO") "ERJ-3GEYJ103V"))
      (libsource (lib "eagle-import") (part "sha2017_rev0_1_0_dev_R0603-DASHES"))
    )
    (comp (ref "R16")
      (value "10k")
      (footprint "eagle-import:R0603-DASHES")
      (fields (field (name "PARTNO") "ERJ-3GEYJ103V"))
      (libsource (lib "eagle-import") (part "sha2017_rev0_1_0_dev_R0603-DASHES"))
    )
    (comp (ref "R17")
      (value "10k")
      (footprint "eagle-import:R0603-DASHES")
      (fields (field (name "PARTNO") "ERJ-3GEYJ103V"))
      (libsource (lib "eagle-import") (part "sha2017_rev0_1_0_dev_R0603-DASHES"))
    )
    (comp (ref "R18")
      (value "10k")
      (footprint "eagle-import:R0603-DASHES")
      (fields (field (name "PARTNO") "ERJ-3GEYJ103V"))
      (libsource (lib "eagle-import") (part "sha2017_rev0_1_0_dev_R0603-DASHES"))
    )
    (comp (ref "R19")
      (value "2R7")
      (footprint "eagle-import:R0603-DASHES")
      (fields (field (name "PARTNO") "ERJ-3GEYJ5R1V"))
      (libsource (lib "eagle-import") (part "sha2017_rev0_1_0_dev_R0603-DASHES"))
    )
    (comp (ref "R22")
      (value "10k")
      (footprint "eagle-import:R0603-DASHES")
      (fields (field (name "PARTNO") "ERJ-3GEYJ103V"))
      (libsource (lib "eagle-import") (part "sha2017_rev0_1_0_dev_R0603-DASHES"))
    )
    (comp (ref "R25")
      (value "10k")
      (footprint "eagle-import:R0603-DASHES")
      (fields (field (name "PARTNO") "ERJ-3GEYJ103V"))
      (libsource (lib "eagle-import") (part "sha2017_rev0_1_0_dev_R0603-DASHES"))
    )
    (comp (ref "R26")
      (value "0R")
      (footprint "eagle-import:R0603-DASHES")
      (fields (field (name "PARTNO") "ERJ-3GEYJ5R1V"))
      (libsource (lib "eagle-import") (part "sha2017_rev0_1_0_dev_R0603-DASHES"))
    )
    (comp (ref "R27")
      (value "10k")
      (footprint "eagle-import:R0603-DASHES")
      (fields (field (name "PARTNO") "ERJ-3GEYJ103V"))
      (libsource (lib "eagle-import") (part "R0603-DASHES"))
    )
    (comp (ref "R28")
      (value "10k")
      (footprint "eagle-import:R0603-DASHES")
      (fields (field (name "PARTNO") "ERJ-3GEYJ103V"))
      (libsource (lib "eagle-import") (part "R0603-DASHES"))
    )
    (comp (ref "R31")
      (value "100k")
      (footprint "eagle-import:R0603-DASHES")
      (fields (field (name "PARTNO") "ERJ-3GEYJ104V"))
      (libsource (lib "eagle-import") (part "sha2017_rev0_1_0_dev_R0603-DASHES"))
    )
    (comp (ref "S1")
      (value "SWITCH-MOMENTARY-2SMD")
      (footprint "eagle-import:TACTILE-SWITCH-SMD")
      (fields (field (name "PARTNO") "SKQGABE010"))
      (libsource (lib "eagle-import") (part "SWITCH-MOMENTARY-2SMD"))
    )
    (comp (ref "S2")
      (value "SWITCH-MOMENTARY-2SMD")
      (footprint "eagle-import:TACTILE-SWITCH-SMD")
      (fields (field (name "PARTNO") "SKQGABE010"))
      (libsource (lib "eagle-import") (part "SWITCH-MOMENTARY-2SMD"))
    )
    (comp (ref "T3")
      (value "MOSFET-PCHANNEL")
      (footprint "eagle-import:SOT23-3")
      (libsource (lib "eagle-import") (part "MOSFET-PCHANNEL"))
    )
    (comp (ref "TP103")
      (value "TEST-POINT3")
      (footprint "eagle-import:PAD.03X.03")
      (fields (field (name "PARTNO") "NAP"))
      (libsource (lib "eagle-import") (part "TEST-POINT3"))
    )
    (comp (ref "TP104")
      (value "TEST-POINT3")
      (footprint "eagle-import:PAD.03X.03")
      (fields (field (name "PARTNO") "NAP"))
      (libsource (lib "eagle-import") (part "TEST-POINT3"))
    )
    (comp (ref "TP105")
      (value "TEST-POINT3")
      (footprint "eagle-import:PAD.03X.03")
      (fields (field (name "PARTNO") "NAP"))
      (libsource (lib "eagle-import") (part "TEST-POINT3"))
    )
    (comp (ref "TP106")
      (value "TEST-POINT3")
      (footprint "eagle-import:PAD.03X.03")
      (fields (field (name "PARTNO") "NAP"))
      (libsource (lib "eagle-import") (part "TEST-POINT3"))
    )
    (comp (ref "TP107")
      (value "TEST-POINT3")
      (footprint "eagle-import:PAD.03X.03")
      (fields (field (name "PARTNO") "NAP"))
      (libsource (lib "eagle-import") (part "TEST-POINT3"))
    )
    (comp (ref "TP108")
      (value "TEST-POINT3")
      (footprint "eagle-import:PAD.03X.03")
      (fields (field (name "PARTNO") "NAP"))
      (libsource (lib "eagle-import") (part "TEST-POINT3"))
    )
    (comp (ref "TP109")
      (value "TEST-POINT3")
      (footprint "eagle-import:PAD.03X.03")
      (fields (field (name "PARTNO") "NAP"))
      (libsource (lib "eagle-import") (part "TEST-POINT3"))
    )
    (comp (ref "TP111")
      (value "TEST-POINT3")
      (footprint "eagle-import:PAD.03X.03")
      (fields (field (name "PARTNO") "NAP"))
      (libsource (lib "eagle-import") (part "TEST-POINT3"))
    )
    (comp (ref "TP113")
      (value "TEST-POINT3")
      (footprint "eagle-import:PAD.03X.03")
      (fields (field (name "PARTNO") "NAP"))
      (libsource (lib "eagle-import") (part "TEST-POINT3"))
    )
    (comp (ref "TP118")
      (value "TEST-POINT3")
      (footprint "eagle-import:PAD.03X.03")
      (fields (field (name "PARTNO") "NAP"))
      (libsource (lib "eagle-import") (part "TEST-POINT3"))
    )
    (comp (ref "TP123")
      (value "TEST-POINT3")
      (footprint "eagle-import:PAD.03X.03")
      (fields (field (name "PARTNO") "NAP"))
      (libsource (lib "eagle-import") (part "TEST-POINT3"))
    )
    (comp (ref "TP124")
      (value "TEST-POINT3")
      (footprint "eagle-import:PAD.03X.03")
      (fields (field (name "PARTNO") "NAP"))
      (libsource (lib "eagle-import") (part "TEST-POINT3"))
    )
    (comp (ref "TP125")
      (value "TEST-POINT3")
      (footprint "eagle-import:PAD.03X.03")
      (fields (field (name "PARTNO") "NAP"))
      (libsource (lib "eagle-import") (part "TEST-POINT3"))
    )
    (comp (ref "TP126")
      (value "TEST-POINT3")
      (footprint "eagle-import:PAD.03X.03")
      (fields (field (name "PARTNO") "NAP"))
      (libsource (lib "eagle-import") (part "TEST-POINT3"))
    )
    (comp (ref "TP127")
      (value "TEST-POINT3")
      (footprint "eagle-import:PAD.03X.03")
      (fields (field (name "PARTNO") "NAP"))
      (libsource (lib "eagle-import") (part "TEST-POINT3"))
    )
    (comp (ref "TP128")
      (value "TEST-POINT3")
      (footprint "eagle-import:PAD.03X.03")
      (fields (field (name "PARTNO") "NAP"))
      (libsource (lib "eagle-import") (part "TEST-POINT3"))
    )
    (comp (ref "TP130")
      (value "TEST-POINT3")
      (footprint "eagle-import:PAD.03X.03")
      (fields (field (name "PARTNO") "NAP"))
      (libsource (lib "eagle-import") (part "TEST-POINT3"))
    )
    (comp (ref "TP131")
      (value "TEST-POINT3")
      (footprint "eagle-import:PAD.03X.03")
      (fields (field (name "PARTNO") "NAP"))
      (libsource (lib "eagle-import") (part "TEST-POINT3"))
    )
    (comp (ref "TP132")
      (value "TEST-POINT3")
      (footprint "eagle-import:PAD.03X.03")
      (fields (field (name "PARTNO") "NAP"))
      (libsource (lib "eagle-import") (part "TEST-POINT3"))
    )
    (comp (ref "TP139")
      (value "TEST-POINT3")
      (footprint "eagle-import:PAD.03X.03")
      (fields (field (name "PARTNO") "NAP"))
      (libsource (lib "eagle-import") (part "TEST-POINT3"))
    )
    (comp (ref "USB1")
      (value "MOLEX-47346-0001")
      (footprint "eagle-import:MOLEX-47364-0001")
      (fields (field (name "PARTNO") "10118192-0001LF"))
      (libsource (lib "eagle-import") (part "MOLEX-47346-0001"))
    )
    (comp (ref "X1")
      (value "68712414022")
      (footprint "eagle-import:68712414022")
      (libsource (lib "eagle-import") (part "68712414022"))
    )
    (comp (ref "X2")
      (value "2908-05WB-MG")
      (footprint "eagle-import:MICRO-SD-SOCKET-PP")
      (libsource (lib "eagle-import") (part "2908-05WB-MG"))
    )
  )
  (nets
    (net (code "1") (name "+3V3") (class "Default")
      (node (ref "C17") (pin "1") (pinfunction "1_1") (pintype "passive"))
      (node (ref "C20") (pin "1") (pinfunction "1_1") (pintype "passive"))
      (node (ref "C22") (pin "1") (pinfunction "1_1") (pintype "passive"))
      (node (ref "C26") (pin "1") (pinfunction "1_1") (pintype "passive"))
      (node (ref "C27") (pin "1") (pinfunction "1_1") (pintype "passive"))
      (node (ref "C30") (pin "1") (pinfunction "1_1") (pintype "passive"))
      (node (ref "C37") (pin "1") (pinfunction "1_1") (pintype "passive"))
      (node (ref "C39") (pin "1") (pinfunction "1_1") (pintype "passive"))
      (node (ref "C43") (pin "1") (pinfunction "1_1") (pintype "passive"))
      (node (ref "C44") (pin "1") (pinfunction "1_1") (pintype "passive"))
      (node (ref "C46") (pin "1") (pinfunction "1_1") (pintype "passive"))
      (node (ref "IC2") (pin "4") (pinfunction "OUT_4") (pintype "passive"))
      (node (ref "IC3") (pin "2") (pinfunction "VCC_2") (pintype "power_in"))
      (node (ref "L1") (pin "1") (pinfunction "1_1") (pintype "passive"))
      (node (ref "R1") (pin "2") (pinfunction "2_2") (pintype "passive"))
      (node (ref "R16") (pin "2") (pinfunction "2_2") (pintype "passive"))
      (node (ref "R22") (pin "1") (pinfunction "1_1") (pintype "passive"))
      (node (ref "R23") (pin "1") (pinfunction "1_1") (pintype "passive"))
      (node (ref "R24") (pin "1") (pinfunction "1_1") (pintype "passive"))
      (node (ref "R26") (pin "1") (pinfunction "1_1") (pintype "passive"))
      (node (ref "R28") (pin "2") (pinfunction "2_2") (pintype "passive"))
      (node (ref "R36") (pin "2") (pinfunction "2_2") (pintype "passive"))
      (node (ref "T3") (pin "2") (pinfunction "S_2") (pintype "passive"))
      (node (ref "TP119") (pin "P$1") (pinfunction "1_P$1") (pintype "bidirectional"))
      (node (ref "U1") (pin "20") (pinfunction "V_DD_20") (pintype "power_in"))
      (node (ref "X1") (pin "10") (pinfunction "10_10") (pintype "passive"))
      (node (ref "X1") (pin "9") (pinfunction "9_9") (pintype "passive"))
    )
    (net (code "2") (name "+5V") (class "Default")
      (node (ref "C11") (pin "1") (pinfunction "1_1") (pintype "passive"))
      (node (ref "C9") (pin "1") (pinfunction "1_1") (pintype "passive"))
      (node (ref "D1") (pin "C") (pinfunction "C_C") (pintype "passive"))
      (node (ref "D3") (pin "A") (pinfunction "A_A") (pintype "passive"))
      (node (ref "F1") (pin "2") (pinfunction "2_2") (pintype "bidirectional"))
      (node (ref "IC1") (pin "7") (pinfunction "REGIN_7") (pintype "passive"))
      (node (ref "IC1") (pin "8") (pinfunction "VBUS_8") (pintype "input"))
      (node (ref "R30") (pin "1") (pinfunction "1_1") (pintype "passive"))
      (node (ref "R4") (pin "2") (pinfunction "2_2") (pintype "passive"))
      (node (ref "R7") (pin "2") (pinfunction "2_2") (pintype "passive"))
      (node (ref "T1") (pin "1") (pinfunction "G_1") (pintype "passive"))
      (node (ref "TP112") (pin "P$1") (pinfunction "1_P$1") (pintype "bidirectional"))
    )
    (net (code "3") (name "3V3_SWITCHED") (class "Default")
      (node (ref "C12") (pin "1") (pinfunction "1_1") (pintype "passive"))
      (node (ref "C31") (pin "1") (pinfunction "1_1") (pintype "passive"))
      (node (ref "C40") (pin "1") (pinfunction "1_1") (pintype "passive"))
      (node (ref "C41") (pin "1") (pinfunction "1_1") (pintype "passive"))
      (node (ref "C7") (pin "1") (pinfunction "1_1") (pintype "passive"))
      (node (ref "R17") (pin "2") (pinfunction "2_2") (pintype "passive"))
      (node (ref "R25") (pin "2") (pinfunction "2_2") (pintype "passive"))
      (node (ref "R31") (pin "1") (pinfunction "1_1") (pintype "passive"))
      (node (ref "R5") (pin "2") (pinfunction "2_2") (pintype "passive"))
      (node (ref "R8") (pin "2") (pinfunction "2_2") (pintype "passive"))
      (node (ref "T3") (pin "3") (pinfunction "D_3") (pintype "passive"))
      (node (ref "TP116") (pin "P$1") (pinfunction "1_P$1") (pintype "bidirectional"))
      (node (ref "X2") (pin "4") (pinfunction "VCC_4") (pintype "bidirectional"))
      (node (ref "X3") (pin "12") (pinfunction "1_12") (pintype "passive"))
    )
    (net (code "4") (name "CHRG_STAT") (class "Default")
      (node (ref "IC4") (pin "7") (pinfunction "CHRG_7") (pintype "bidirectional"))
      (node (ref "R36") (pin "1") (pinfunction "1_1") (pintype "passive"))
      (node (ref "U1") (pin "17") (pinfunction "ELE9_17") (pintype "output"))
    )
    (net (code "5") (name "ESP32_FLASH") (class "Default")
      (node (ref "D2") (pin "C") (pinfunction "C_C") (pintype "passive"))
      (node (ref "IC3") (pin "25") (pinfunction "IO0_25") (pintype "bidirectional"))
      (node (ref "Q4") (pin "3") (pinfunction "C_3") (pintype "passive"))
      (node (ref "R16") (pin "1") (pinfunction "1_1") (pintype "passive"))
      (node (ref "S2") (pin "3") (pinfunction "2_3") (pintype "passive"))
      (node (ref "TP120") (pin "P$1") (pinfunction "1_P$1") (pintype "bidirectional"))
    )
    (net (code "6") (name "ESP32_RX") (class "Default")
      (node (ref "D4") (pin "C") (pinfunction "C_C") (pintype "passive"))
      (node (ref "IC1") (pin "26") (pinfunction "TXD_26") (pintype "output"))
      (node (ref "IC3") (pin "34") (pinfunction "RXD0_34") (pintype "bidirectional"))
      (node (ref "TP133") (pin "P$1") (pinfunction "1_P$1") (pintype "bidirectional"))
    )
    (net (code "7") (name "ESP32_TX") (class "Default")
      (node (ref "D5") (pin "C") (pinfunction "C_C") (pintype "passive"))
      (node (ref "IC1") (pin "25") (pinfunction "RXD_25") (pintype "input"))
      (node (ref "IC3") (pin "35") (pinfunction "TXD0_35") (pintype "bidirectional"))
      (node (ref "TP134") (pin "P$1") (pinfunction "1_P$1") (pintype "bidirectional"))
    )
    (net (code "8") (name "ESP32_~{RESET}") (class "Default")
      (node (ref "IC3") (pin "3") (pinfunction "EN_3") (pintype "bidirectional"))
      (node (ref "Q3") (pin "3") (pinfunction "C_3") (pintype "passive"))
      (node (ref "R22") (pin "2") (pinfunction "2_2") (pintype "passive"))
      (node (ref "S1") (pin "3") (pinfunction "2_3") (pintype "passive"))
      (node (ref "TP121") (pin "P$1") (pinfunction "1_P$1") (pintype "bidirectional"))
    )
    (net (code "9") (name "EXTIO-0") (class "Default")
      (node (ref "IC3") (pin "9") (pinfunction "IO33_9") (pintype "bidirectional"))
      (node (ref "X3") (pin "3") (pinfunction "10_3") (pintype "passive"))
    )
    (net (code "10") (name "EXTIO-1") (class "Default")
      (node (ref "IC3") (pin "27") (pinfunction "IO16_27") (pintype "bidirectional"))
      (node (ref "X3") (pin "4") (pinfunction "9_4") (pintype "passive"))
    )
    (net (code "11") (name "EXTIO-2") (class "Default")
      (node (ref "IC3") (pin "28") (pinfunction "IO17_28") (pintype "bidirectional"))
      (node (ref "X3") (pin "5") (pinfunction "8_5") (pintype "passive"))
    )
    (net (code "12") (name "EXTIO-3") (class "Default")
      (node (ref "IC3") (pin "26") (pinfunction "IO4_26") (pintype "bidirectional"))
      (node (ref "X3") (pin "9") (pinfunction "4_9") (pintype "passive"))
    )
    (net (code "13") (name "EXTIO-4") (class "Default")
      (node (ref "IC3") (pin "14") (pinfunction "IO12_14") (pintype "bidirectional"))
      (node (ref "X3") (pin "10") (pinfunction "3_10") (pintype "passive"))
    )
    (net (code "14") (name "GDR") (class "Default")
      (node (ref "Q5") (pin "1") (pinfunction "G_1") (pintype "passive"))
      (node (ref "TP124") (pin "P$1") (pinfunction "1_P$1") (pintype "bidirectional"))
      (node (ref "X1") (pin "23") (pinfunction "23_23") (pintype "passive"))
    )
    (net (code "15") (name "GND") (class "Default")
      (node (ref "$$U$1") (pin "P$1") (pinfunction "P$1_P$1") (pintype "bidirectional"))
      (node (ref "$$U$2") (pin "P$1") (pinfunction "P$1_P$1") (pintype "bidirectional"))
      (node (ref "$$U$3") (pin "P$1") (pinfunction "P$1_P$1") (pintype "bidirectional"))
      (node (ref "$$U$4") (pin "P$1") (pinfunction "P$1_P$1") (pintype "bidirectional"))
      (node (ref "$$U$5") (pin "P$1") (pinfunction "P$1_P$1") (pintype "bidirectional"))
      (node (ref "$$U$6") (pin "P$1") (pinfunction "P$1_P$1") (pintype "bidirectional"))
      (node (ref "$$U$7") (pin "P$1") (pinfunction "P$1_P$1") (pintype "bidirectional"))
      (node (ref "$$U$8") (pin "P$1") (pinfunction "P$1_P$1") (pintype "bidirectional"))
      (node (ref "$$U$9") (pin "P$1") (pinfunction "P$1_P$1") (pintype "bidirectional"))
      (node (ref "C1") (pin "1") (pinfunction "1_1") (pintype "passive"))
      (node (ref "C10") (pin "2") (pinfunction "2_2") (pintype "passive"))
      (node (ref "C11") (pin "2") (pinfunction "2_2") (pintype "passive"))
      (node (ref "C12") (pin "2") (pinfunction "2_2") (pintype "passive"))
      (node (ref "C13") (pin "2") (pinfunction "2_2") (pintype "passive"))
      (node (ref "C14") (pin "2") (pinfunction "2_2") (pintype "passive"))
      (node (ref "C15") (pin "2") (pinfunction "2_2") (pintype "passive"))
      (node (ref "C16") (pin "2") (pinfunction "2_2") (pintype "passive"))
      (node (ref "C17") (pin "2") (pinfunction "2_2") (pintype "passive"))
      (node (ref "C18") (pin "2") (pinfunction "2_2") (pintype "passive"))
      (node (ref "C19") (pin "1") (pinfunction "1_1") (pintype "passive"))
      (node (ref "C2") (pin "1") (pinfunction "1_1") (pintype "passive"))
      (node (ref "C20") (pin "2") (pinfunction "2_2") (pintype "passive"))
      (node (ref "C21") (pin "1") (pinfunction "1_1") (pintype "passive"))
      (node (ref "C22") (pin "2") (pinfunction "2_2") (pintype "passive"))
      (node (ref "C23") (pin "1") (pinfunction "1_1") (pintype "passive"))
      (node (ref "C24") (pin "2") (pinfunction "2_2") (pintype "passive"))
      (node (ref "C26") (pin "2") (pinfunction "2_2") (pintype "passive"))
      (node (ref "C27") (pin "2") (pinfunction "2_2") (pintype "passive"))
      (node (ref "C28") (pin "1") (pinfunction "1_1") (pintype "passive"))
      (node (ref "C29") (pin "1") (pinfunction "1_1") (pintype "passive"))
      (node (ref "C3") (pin "1") (pinfunction "1_1") (pintype "passive"))
      (node (ref "C30") (pin "2") (pinfunction "2_2") (pintype "passive"))
      (node (ref "C31") (pin "2") (pinfunction "2_2") (pintype "passive"))
      (node (ref "C32") (pin "1") (pinfunction "1_1") (pintype "passive"))
      (node (ref "C33") (pin "1") (pinfunction "1_1") (pintype "passive"))
      (node (ref "C34") (pin "2") (pinfunction "2_2") (pintype "passive"))
      (node (ref "C35") (pin "1") (pinfunction "1_1") (pintype "passive"))
      (node (ref "C36") (pin "1") (pinfunction "1_1") (pintype "passive"))
      (node (ref "C37") (pin "2") (pinfunction "2_2") (pintype "passive"))
      (node (ref "C38") (pin "1") (pinfunction "1_1") (pintype "passive"))
      (node (ref "C39") (pin "2") (pinfunction "2_2") (pintype "passive"))
      (node (ref "C4") (pin "1") (pinfunction "1_1") (pintype "passive"))
      (node (ref "C40") (pin "2") (pinfunction "2_2") (pintype "passive"))
      (node (ref "C41") (pin "2") (pinfunction "2_2") (pintype "passive"))
      (node (ref "C42") (pin "2") (pinfunction "2_2") (pintype "passive"))
      (node (ref "C43") (pin "2") (pinfunction "2_2") (pintype "passive"))
      (node (ref "C44") (pin "2") (pinfunction "2_2") (pintype "passive"))
      (node (ref "C45") (pin "2") (pinfunction "2_2") (pintype "passive"))
      (node (ref "C46") (pin "2") (pinfunction "2_2") (pintype "passive"))
      (node (ref "C5") (pin "1") (pinfunction "1_1") (pintype "passive"))
      (node (ref "C6") (pin "1") (pinfunction "1_1") (pintype "passive"))
      (node (ref "C7") (pin "2") (pinfunction "2_2") (pintype "passive"))
      (node (ref "C8") (pin "2") (pinfunction "2_2") (pintype "passive"))
      (node (ref "C9") (pin "2") (pinfunction "2_2") (pintype "passive"))
      (node (ref "D1") (pin "A") (pinfunction "A_A") (pintype "passive"))
      (node (ref "D100") (pin "3") (pinfunction "VSS_3") (pintype "power_in"))
      (node (ref "D101") (pin "3") (pinfunction "VSS_3") (pintype "power_in"))
      (node (ref "D102") (pin "3") (pinfunction "VSS_3") (pintype "power_in"))
      (node (ref "D103") (pin "3") (pinfunction "VSS_3") (pintype "power_in"))
      (node (ref "D104") (pin "3") (pinfunction "VSS_3") (pintype "power_in"))
      (node (ref "D105") (pin "3") (pinfunction "VSS_3") (pintype "power_in"))
      (node (ref "D6") (pin "C") (pinfunction "C_C") (pintype "passive"))
      (node (ref "D7") (pin "C") (pinfunction "C_C") (pintype "passive"))
      (node (ref "IC1") (pin "3") (pinfunction "GND_3") (pintype "power_in"))
      (node (ref "IC1") (pin "EXP") (pinfunction "GND_EXP") (pintype "power_in"))
      (node (ref "IC1") (pin "M") (pinfunction "GND_M") (pintype "power_in"))
      (node (ref "IC2") (pin "1") (pinfunction "ADJ_1") (pintype "input"))
      (node (ref "IC3") (pin "0") (pinfunction "GND_0") (pintype "power_in"))
      (node (ref "IC3") (pin "1") (pinfunction "GND_1") (pintype "power_in"))
      (node (ref "IC3") (pin "15") (pinfunction "GND_15") (pintype "power_in"))
      (node (ref "IC3") (pin "38") (pinfunction "GND_38") (pintype "power_in"))
      (node (ref "IC4") (pin "3") (pinfunction "GND_3") (pintype "bidirectional"))
      (node (ref "Q1") (pin "2") (pinfunction "E_2") (pintype "passive"))
      (node (ref "Q2") (pin "2") (pinfunction "E_2") (pintype "passive"))
      (node (ref "Q6") (pin "2") (pinfunction "E_2") (pintype "passive"))
      (node (ref "R19") (pin "2") (pinfunction "2_2") (pintype "passive"))
      (node (ref "R20") (pin "1") (pinfunction "1_1") (pintype "passive"))
      (node (ref "R35") (pin "2") (pinfunction "2_2") (pintype "passive"))
      (node (ref "R37") (pin "1") (pinfunction "1_1") (pintype "passive"))
      (node (ref "R4") (pin "1") (pinfunction "1_1") (pintype "passive"))
      (node (ref "R6") (pin "1") (pinfunction "1_1") (pintype "passive"))
      (node (ref "S1") (pin "1") (pinfunction "1_1") (pintype "passive"))
      (node (ref "S2") (pin "1") (pinfunction "1_1") (pintype "passive"))
      (node (ref "SJ3") (pin "1") (pinfunction "1_1") (pintype "passive"))
      (node (ref "TP1") (pin "P$1") (pinfunction "1_P$1") (pintype "bidirectional"))
      (node (ref "TP102") (pin "P$1") (pinfunction "1_P$1") (pintype "bidirectional"))
      (node (ref "TP103") (pin "P$1") (pinfunction "1_P$1") (pintype "bidirectional"))
      (node (ref "TP106") (pin "P$1") (pinfunction "1_P$1") (pintype "bidirectional"))
      (node (ref "TP122") (pin "P$1") (pinfunction "1_P$1") (pintype "bidirectional"))
      (node (ref "TP125") (pin "P$1") (pinfunction "1_P$1") (pintype "bidirectional"))
      (node (ref "TP135") (pin "P$1") (pinfunction "1_P$1") (pintype "bidirectional"))
      (node (ref "TP140") (pin "P$1") (pinfunction "1_P$1") (pintype "bidirectional"))
      (node (ref "U$10") (pin "P$1") (pinfunction "P$1_P$1") (pintype "bidirectional"))
      (node (ref "U$11") (pin "P$1") (pinfunction "P$1_P$1") (pintype "bidirectional"))
      (node (ref "U$12") (pin "P$1") (pinfunction "P$1_P$1") (pintype "bidirectional"))
      (node (ref "U$13") (pin "P$1") (pinfunction "P$1_P$1") (pintype "bidirectional"))
      (node (ref "U$14") (pin "P$1") (pinfunction "P$1_P$1") (pintype "bidirectional"))
      (node (ref "U$15") (pin "P$1") (pinfunction "P$1_P$1") (pintype "bidirectional"))
      (node (ref "U$16") (pin "P$1") (pinfunction "P$1_P$1") (pintype "bidirectional"))
      (node (ref "U$17") (pin "P$1") (pinfunction "P$1_P$1") (pintype "bidirectional"))
      (node (ref "U$18") (pin "P$1") (pinfunction "P$1_P$1") (pintype "bidirectional"))
      (node (ref "U$19") (pin "P$1") (pinfunction "P$1_P$1") (pintype "bidirectional"))
      (node (ref "U$2") (pin "P$1") (pinfunction "P$1_P$1") (pintype "bidirectional"))
      (node (ref "U$20") (pin "P$1") (pinfunction "P$1_P$1") (pintype "bidirectional"))
      (node (ref "U$21") (pin "P$1") (pinfunction "P$1_P$1") (pintype "bidirectional"))
      (node (ref "U$22") (pin "P$1") (pinfunction "P$1_P$1") (pintype "bidirectional"))
      (node (ref "U$23") (pin "P$1") (pinfunction "P$1_P$1") (pintype "bidirectional"))
      (node (ref "U$3") (pin "P$1") (pinfunction "P$1_P$1") (pintype "bidirectional"))
      (node (ref "U$4") (pin "P$1") (pinfunction "P$1_P$1") (pintype "bidirectional"))
      (node (ref "U$5") (pin "P$1") (pinfunction "P$1_P$1") (pintype "bidirectional"))
      (node (ref "U$6") (pin "P$1") (pinfunction "P$1_P$1") (pintype "bidirectional"))
      (node (ref "U1") (pin "4") (pinfunction "ADDR_4") (pintype "input"))
      (node (ref "U1") (pin "6") (pinfunction "V_SS_6") (pintype "power_in"))
      (node (ref "USB1") (pin "5") (pinfunction "5_5") (pintype "input"))
      (node (ref "USB1") (pin "GND1") (pinfunction "GND1_GND1") (pintype "bidirectional"))
      (node (ref "USB1") (pin "GND2") (pinfunction "GND2_GND2") (pintype "bidirectional"))
      (node (ref "USB1") (pin "GND3") (pinfunction "GND3_GND3") (pintype "bidirectional"))
      (node (ref "USB1") (pin "GND4") (pinfunction "GND4_GND4") (pintype "bidirectional"))
      (node (ref "X1") (pin "17") (pinfunction "17_17") (pintype "passive"))
      (node (ref "X1") (pin "8") (pinfunction "8_8") (pintype "passive"))
      (node (ref "X2") (pin "6") (pinfunction "GND_6") (pintype "bidirectional"))
      (node (ref "X2") (pin "CD2") (pinfunction "SHIELD_CD2") (pintype "bidirectional"))
      (node (ref "X2") (pin "GND1") (pinfunction "SHIELD_GND1") (pintype "bidirectional"))
      (node (ref "X2") (pin "GND3") (pinfunction "SHIELD_GND3") (pintype "bidirectional"))
      (node (ref "X3") (pin "1") (pinfunction "12_1") (pintype "passive"))
      (node (ref "X3") (pin "11") (pinfunction "2_11") (pintype "passive"))
      (node (ref "X4") (pin "2") (pinfunction "1_2") (pintype "passive"))
    )
    (net (code "16") (name "I2C_INT") (class "Default")
      (node (ref "IC3") (pin "10") (pinfunction "IO25_10") (pintype "bidirectional"))
      (node (ref "R1") (pin "1") (pinfunction "1_1") (pintype "passive"))
      (node (ref "U1") (pin "1") (pinfunction "~{IRQ}_1") (pintype "input"))
    )
    (net (code "17") (name "I2C_SCL") (class "Default")
      (node (ref "IC3") (pin "12") (pinfunction "IO27_12") (pintype "bidirectional"))
      (node (ref "R24") (pin "2") (pinfunction "2_2") (pintype "passive"))
      (node (ref "TP100") (pin "P$1") (pinfunction "1_P$1") (pintype "bidirectional"))
      (node (ref "TP114") (pin "P$1") (pinfunction "1_P$1") (pintype "bidirectional"))
      (node (ref "TP3") (pin "P$1") (pinfunction "1_P$1") (pintype "bidirectional"))
      (node (ref "U1") (pin "2") (pinfunction "SCL_2") (pintype "input"))
      (node (ref "X3") (pin "6") (pinfunction "7_6") (pintype "passive"))
    )
    (net (code "18") (name "I2C_SDA") (class "Default")
      (node (ref "IC3") (pin "11") (pinfunction "IO26_11") (pintype "bidirectional"))
      (node (ref "R23") (pin "2") (pinfunction "2_2") (pintype "passive"))
      (node (ref "TP101") (pin "P$1") (pinfunction "1_P$1") (pintype "bidirectional"))
      (node (ref "TP115") (pin "P$1") (pinfunction "1_P$1") (pintype "bidirectional"))
      (node (ref "TP2") (pin "P$1") (pinfunction "1_P$1") (pintype "bidirectional"))
      (node (ref "U1") (pin "3") (pinfunction "SDA_3") (pintype "input"))
      (node (ref "X3") (pin "7") (pinfunction "6_7") (pintype "passive"))
    )
    (net (code "19") (name "LCD_BUSY") (class "Default")
      (node (ref "IC3") (pin "36") (pinfunction "IO22_36") (pintype "bidirectional"))
      (node (ref "TP118") (pin "P$1") (pinfunction "1_P$1") (pintype "bidirectional"))
      (node (ref "X1") (pin "16") (pinfunction "16_16") (pintype "passive"))
    )
    (net (code "20") (name "LCD_CS") (class "Default")
      (node (ref "IC3") (pin "31") (pinfunction "IO19_31") (pintype "bidirectional"))
      (node (ref "TP109") (pin "P$1") (pinfunction "1_P$1") (pintype "bidirectional"))
      (node (ref "X1") (pin "13") (pinfunction "13_13") (pintype "passive"))
    )
    (net (code "21") (name "LCD_D{slash}~{S}") (class "Default")
      (node (ref "IC3") (pin "33") (pinfunction "IO21_33") (pintype "bidirectional"))
      (node (ref "TP111") (pin "P$1") (pinfunction "1_P$1") (pintype "bidirectional"))
      (node (ref "X1") (pin "14") (pinfunction "14_14") (pintype "passive"))
    )
    (net (code "22") (name "LCD_MOSI") (class "Default")
      (node (ref "IC3") (pin "29") (pinfunction "IO5_29") (pintype "bidirectional"))
      (node (ref "TP107") (pin "P$1") (pinfunction "1_P$1") (pintype "bidirectional"))
      (node (ref "X1") (pin "11") (pinfunction "11_11") (pintype "passive"))
    )
    (net (code "23") (name "LCD_SCK") (class "Default")
      (node (ref "IC3") (pin "30") (pinfunction "IO18_30") (pintype "bidirectional"))
      (node (ref "TP108") (pin "P$1") (pinfunction "1_P$1") (pintype "bidirectional"))
      (node (ref "X1") (pin "12") (pinfunction "12_12") (pintype "passive"))
    )
    (net (code "24") (name "LCD_VDD") (class "Default")
      (node (ref "C42") (pin "1") (pinfunction "1_1") (pintype "passive"))
      (node (ref "R26") (pin "2") (pinfunction "2_2") (pintype "passive"))
      (node (ref "X1") (pin "7") (pinfunction "7_7") (pintype "passive"))
    )
    (net (code "25") (name "LCD_~{RESET}") (class "Default")
      (node (ref "IC3") (pin "37") (pinfunction "IO23_37") (pintype "bidirectional"))
      (node (ref "TP113") (pin "P$1") (pinfunction "1_P$1") (pintype "bidirectional"))
      (node (ref "X1") (pin "15") (pinfunction "15_15") (pintype "passive"))
    )
    (net (code "26") (name "Net-(C25-Pad1)") (class "Default")
      (node (ref "C25") (pin "1") (pinfunction "1_1") (pintype "passive"))
      (node (ref "D7") (pin "A") (pinfunction "A_A") (pintype "passive"))
      (node (ref "D8") (pin "C") (pinfunction "C_C") (pintype "passive"))
    )
    (net (code "27") (name "Net-(D4-PadA)") (class "Default")
      (node (ref "D4") (pin "A") (pinfunction "A_A") (pintype "passive"))
      (node (ref "R3") (pin "1") (pinfunction "1_1") (pintype "passive"))
    )
    (net (code "28") (name "Net-(D5-PadA)") (class "Default")
      (node (ref "D5") (pin "A") (pinfunction "A_A") (pintype "passive"))
      (node (ref "R14") (pin "1") (pinfunction "1_1") (pintype "passive"))
    )
    (net (code "29") (name "Net-(D6-PadA)") (class "Default")
      (node (ref "D6") (pin "A") (pinfunction "A_A") (pintype "passive"))
      (node (ref "R12") (pin "1") (pinfunction "1_1") (pintype "passive"))
    )
    (net (code "30") (name "Net-(D100-DIN)") (class "Default")
      (node (ref "D100") (pin "4") (pinfunction "DIN_4") (pintype "input"))
      (node (ref "D101") (pin "2") (pinfunction "DOUT_2") (pintype "output"))
    )
    (net (code "31") (name "Net-(D101-DIN)") (class "Default")
      (node (ref "D101") (pin "4") (pinfunction "DIN_4") (pintype "input"))
      (node (ref "D102") (pin "2") (pinfunction "DOUT_2") (pintype "output"))
    )
    (net (code "32") (name "Net-(D102-DIN)") (class "Default")
      (node (ref "D102") (pin "4") (pinfunction "DIN_4") (pintype "input"))
      (node (ref "D103") (pin "2") (pinfunction "DOUT_2") (pintype "output"))
    )
    (net (code "33") (name "Net-(D103-DIN)") (class "Default")
      (node (ref "D103") (pin "4") (pinfunction "DIN_4") (pintype "input"))
      (node (ref "D104") (pin "2") (pinfunction "DOUT_2") (pintype "output"))
    )
    (net (code "34") (name "Net-(D104-DIN)") (class "Default")
      (node (ref "D104") (pin "4") (pinfunction "DIN_4") (pintype "input"))
      (node (ref "D105") (pin "2") (pinfunction "DOUT_2") (pintype "output"))
    )
    (net (code "35") (name "Net-(IC1-DTR)") (class "Default")
      (node (ref "IC1") (pin "28") (pinfunction "DTR_28") (pintype "output"))
      (node (ref "Q4") (pin "2") (pinfunction "E_2") (pintype "passive"))
      (node (ref "R18") (pin "1") (pinfunction "1_1") (pintype "passive"))
    )
    (net (code "36") (name "Net-(IC1-RTS)") (class "Default")
      (node (ref "IC1") (pin "24") (pinfunction "RTS_24") (pintype "output"))
      (node (ref "Q3") (pin "2") (pinfunction "E_2") (pintype "passive"))
      (node (ref "R15") (pin "1") (pinfunction "1_1") (pintype "passive"))
    )
    (net (code "37") (name "Net-(IC1-~{RST})") (class "Default")
      (node (ref "IC1") (pin "9") (pinfunction "~{RST}_9") (pintype "bidirectional"))
      (node (ref "R13") (pin "2") (pinfunction "2_2") (pintype "passive"))
    )
    (net (code "38") (name "Net-(IC3-CLK)") (class "Default")
      (node (ref "IC3") (pin "20") (pinfunction "CLK_20") (pintype "bidirectional"))
      (node (ref "TP130") (pin "P$1") (pinfunction "1_P$1") (pintype "bidirectional"))
    )
    (net (code "39") (name "Net-(IC3-CND)") (class "Default")
      (node (ref "IC3") (pin "19") (pinfunction "CND_19") (pintype "bidirectional"))
      (node (ref "TP128") (pin "P$1") (pinfunction "1_P$1") (pintype "bidirectional"))
    )
    (net (code "40") (name "Net-(IC3-SD0)") (class "Default")
      (node (ref "IC3") (pin "21") (pinfunction "SD0_21") (pintype "bidirectional"))
      (node (ref "TP131") (pin "P$1") (pinfunction "1_P$1") (pintype "bidirectional"))
    )
    (net (code "41") (name "Net-(IC3-SD1)") (class "Default")
      (node (ref "IC3") (pin "22") (pinfunction "SD1_22") (pintype "bidirectional"))
      (node (ref "TP132") (pin "P$1") (pinfunction "1_P$1") (pintype "bidirectional"))
    )
    (net (code "42") (name "Net-(IC3-SD2)") (class "Default")
      (node (ref "IC3") (pin "17") (pinfunction "SD2_17") (pintype "bidirectional"))
      (node (ref "TP126") (pin "P$1") (pinfunction "1_P$1") (pintype "bidirectional"))
    )
    (net (code "43") (name "Net-(IC3-SD3)") (class "Default")
      (node (ref "IC3") (pin "18") (pinfunction "SD3_18") (pintype "bidirectional"))
      (node (ref "TP127") (pin "P$1") (pinfunction "1_P$1") (pintype "bidirectional"))
    )
    (net (code "44") (name "Net-(IC3-SENSOR_VN)") (class "Default")
      (node (ref "C29") (pin "2") (pinfunction "2_2") (pintype "passive"))
      (node (ref "IC3") (pin "5") (pinfunction "SENSOR_VN_5") (pintype "bidirectional"))
    )
    (net (code "45") (name "Net-(IC3-SENSOR_VP)") (class "Default")
      (node (ref "C28") (pin "2") (pinfunction "2_2") (pintype "passive"))
      (node (ref "IC3") (pin "4") (pinfunction "SENSOR_VP_4") (pintype "bidirectional"))
    )
    (net (code "46") (name "Net-(IC4-BAT)") (class "Default")
      (node (ref "C34") (pin "1") (pinfunction "1_1") (pintype "passive"))
      (node (ref "F2") (pin "1") (pinfunction "1_1") (pintype "bidirectional"))
      (node (ref "IC4") (pin "5") (pinfunction "BAT_5") (pintype "bidirectional"))
      (node (ref "X4") (pin "3") (pinfunction "1_3") (pintype "passive"))
    )
    (net (code "47") (name "Net-(IC4-CE)") (class "Default")
      (node (ref "C23") (pin "2") (pinfunction "2_2") (pintype "passive"))
      (node (ref "C24") (pin "1") (pinfunction "1_1") (pintype "passive"))
      (node (ref "IC4") (pin "4") (pinfunction "VCC_4") (pintype "bidirectional"))
      (node (ref "IC4") (pin "8") (pinfunction "CE_8") (pintype "bidirectional"))
      (node (ref "R30") (pin "2") (pinfunction "2_2") (pintype "passive"))
      (node (ref "R32") (pin "2") (pinfunction "2_2") (pintype "passive"))
    )
    (net (code "48") (name "Net-(IC4-PROG)") (class "Default")
      (node (ref "IC4") (pin "2") (pinfunction "PROG_2") (pintype "bidirectional"))
      (node (ref "R29") (pin "1") (pinfunction "1_1") (pintype "passive"))
    )
    (net (code "49") (name "Net-(M1-Pad+)") (class "Default")
      (node (ref "M1") (pin "+") (pinfunction "+_+") (pintype "bidirectional"))
      (node (ref "R2") (pin "1") (pinfunction "1_1") (pintype "passive"))
    )
    (net (code "50") (name "Net-(Q1-B)") (class "Default")
      (node (ref "Q1") (pin "1") (pinfunction "B_1") (pintype "passive"))
      (node (ref "R10") (pin "2") (pinfunction "2_2") (pintype "passive"))
    )
    (net (code "51") (name "Net-(Q1-C)") (class "Default")
      (node (ref "Q1") (pin "3") (pinfunction "C_3") (pintype "passive"))
      (node (ref "R9") (pin "1") (pinfunction "1_1") (pintype "passive"))
      (node (ref "T2") (pin "1") (pinfunction "G_1") (pintype "passive"))
    )
    (net (code "52") (name "Net-(Q2-B)") (class "Default")
      (node (ref "Q2") (pin "1") (pinfunction "B_1") (pintype "passive"))
      (node (ref "R11") (pin "1") (pinfunction "1_1") (pintype "passive"))
    )
    (net (code "53") (name "Net-(Q2-C)") (class "Default")
      (node (ref "M1") (pin "-") (pinfunction "-_-") (pintype "bidirectional"))
      (node (ref "Q2") (pin "3") (pinfunction "C_3") (pintype "passive"))
    )
    (net (code "54") (name "Net-(Q3-B)") (class "Default")
      (node (ref "Q3") (pin "1") (pinfunction "B_1") (pintype "passive"))
      (node (ref "R18") (pin "2") (pinfunction "2_2") (pintype "passive"))
    )
    (net (code "55") (name "Net-(Q4-B)") (class "Default")
      (node (ref "Q4") (pin "1") (pinfunction "B_1") (pintype "passive"))
      (node (ref "R15") (pin "2") (pinfunction "2_2") (pintype "passive"))
    )
    (net (code "56") (name "Net-(Q5-D)") (class "Default")
      (node (ref "C25") (pin "2") (pinfunction "2_2") (pintype "passive"))
      (node (ref "D9") (pin "A") (pinfunction "A_A") (pintype "passive"))
      (node (ref "L1") (pin "2") (pinfunction "2_2") (pintype "passive"))
      (node (ref "Q5") (pin "3") (pinfunction "D_3") (pintype "passive"))
    )
    (net (code "57") (name "Net-(Q6-B)") (class "Default")
      (node (ref "Q6") (pin "1") (pinfunction "B_1") (pintype "passive"))
      (node (ref "R27") (pin "2") (pinfunction "2_2") (pintype "passive"))
    )
    (net (code "58") (name "Net-(Q6-C)") (class "Default")
      (node (ref "Q6") (pin "3") (pinfunction "C_3") (pintype "passive"))
      (node (ref "R28") (pin "1") (pinfunction "1_1") (pintype "passive"))
      (node (ref "T3") (pin "1") (pinfunction "G_1") (pintype "passive"))
    )
    (net (code "59") (name "Net-(R29-Pad2)") (class "Default")
      (node (ref "R29") (pin "2") (pinfunction "2_2") (pintype "passive"))
      (node (ref "R35") (pin "1") (pinfunction "1_1") (pintype "passive"))
      (node (ref "SJ3") (pin "2") (pinfunction "2_2") (pintype "passive"))
    )
    (net (code "60") (name "Net-(TOUCH_SEL-DOWN)") (class "Default")
      (node (ref "TOUCH_SEL") (pin "D") (pinfunction "DOWN_D") (pintype "bidirectional"))
      (node (ref "U1") (pin "12") (pinfunction "ELE4_12") (pintype "output"))
    )
    (net (code "61") (name "Net-(TOUCH_SEL-LEFT)") (class "Default")
      (node (ref "TOUCH_SEL") (pin "L") (pinfunction "LEFT_L") (pintype "bidirectional"))
      (node (ref "U1") (pin "15") (pinfunction "ELE7_15") (pintype "output"))
    )
    (net (code "62") (name "Net-(TOUCH_SEL-RIGHT)") (class "Default")
      (node (ref "TOUCH_SEL") (pin "R") (pinfunction "RIGHT_R") (pintype "bidirectional"))
      (node (ref "U1") (pin "13") (pinfunction "ELE5_13") (pintype "output"))
    )
    (net (code "63") (name "Net-(TP139-1)") (class "Default")
      (node (ref "F1") (pin "1") (pinfunction "1_1") (pintype "bidirectional"))
      (node (ref "TP139") (pin "P$1") (pinfunction "1_P$1") (pintype "bidirectional"))
      (node (ref "USB1") (pin "1") (pinfunction "1_1") (pintype "input"))
    )
    (net (code "64") (name "Net-(U1-ELE0)") (class "Default")
      (node (ref "TOUCH_A") (pin "P$1") (pinfunction "P$1_P$1") (pintype "bidirectional"))
      (node (ref "U1") (pin "8") (pinfunction "ELE0_8") (pintype "output"))
    )
    (net (code "65") (name "Net-(U1-ELE1)") (class "Default")
      (node (ref "TOUCH_B") (pin "P$1") (pinfunction "P$1_P$1") (pintype "bidirectional"))
      (node (ref "U1") (pin "9") (pinfunction "ELE1_9") (pintype "output"))
    )
    (net (code "66") (name "Net-(U1-ELE2)") (class "Default")
      (node (ref "TOUCH_START") (pin "P$1") (pinfunction "P$1_P$1") (pintype "bidirectional"))
      (node (ref "U1") (pin "10") (pinfunction "ELE2_10") (pintype "output"))
    )
    (net (code "67") (name "Net-(U1-ELE3)") (class "Default")
      (node (ref "TOUCH_SELECT") (pin "P$1") (pinfunction "P$1_P$1") (pintype "bidirectional"))
      (node (ref "U1") (pin "11") (pinfunction "ELE3_11") (pintype "output"))
    )
    (net (code "68") (name "Net-(U1-ELE6)") (class "Default")
      (node (ref "TOUCH_SEL") (pin "UP") (pinfunction "UP_UP") (pintype "bidirectional"))
      (node (ref "U1") (pin "14") (pinfunction "ELE6_14") (pintype "output"))
    )
    (net (code "69") (name "Net-(U1-REXT)") (class "Default")
      (node (ref "R37") (pin "2") (pinfunction "2_2") (pintype "passive"))
      (node (ref "U1") (pin "7") (pinfunction "REXT_7") (pintype "input"))
    )
    (net (code "70") (name "Net-(U1-V_REG)") (class "Default")
      (node (ref "C45") (pin "1") (pinfunction "1_1") (pintype "passive"))
      (node (ref "U1") (pin "5") (pinfunction "V_REG_5") (pintype "input"))
    )
    (net (code "71") (name "PREVGH") (class "Default")
      (node (ref "C32") (pin "2") (pinfunction "2_2") (pintype "passive"))
      (node (ref "D9") (pin "C") (pinfunction "C_C") (pintype "passive"))
      (node (ref "TP104") (pin "P$1") (pinfunction "1_P$1") (pintype "bidirectional"))
      (node (ref "X1") (pin "4") (pinfunction "4_4") (pintype "passive"))
    )
    (net (code "72") (name "PREVGL") (class "Default")
      (node (ref "C36") (pin "2") (pinfunction "2_2") (pintype "passive"))
      (node (ref "D8") (pin "A") (pinfunction "A_A") (pintype "passive"))
      (node (ref "TP105") (pin "P$1") (pinfunction "1_P$1") (pintype "bidirectional"))
      (node (ref "X1") (pin "2") (pinfunction "2_2") (pintype "passive"))
    )
    (net (code "73") (name "RESE") (class "Default")
      (node (ref "Q5") (pin "2") (pinfunction "S_2") (pintype "passive"))
      (node (ref "R19") (pin "1") (pinfunction "1_1") (pintype "passive"))
      (node (ref "TP123") (pin "P$1") (pinfunction "1_P$1") (pintype "bidirectional"))
      (node (ref "X1") (pin "22") (pinfunction "22_22") (pintype "passive"))
    )
    (net (code "74") (name "SD_CD") (class "Default")
      (node (ref "R31") (pin "2") (pinfunction "2_2") (pintype "passive"))
      (node (ref "U1") (pin "19") (pinfunction "ELE11_19") (pintype "output"))
      (node (ref "X2") (pin "CD1") (pinfunction "SHIELD_CD1") (pintype "bidirectional"))
    )
    (net (code "75") (name "SD_CLK") (class "Default")
      (node (ref "IC3") (pin "13") (pinfunction "IO14_13") (pintype "bidirectional"))
      (node (ref "R25") (pin "1") (pinfunction "1_1") (pintype "passive"))
      (node (ref "X2") (pin "5") (pinfunction "SCK_5") (pintype "bidirectional"))
    )
    (net (code "76") (name "SD_CMD") (class "Default")
      (node (ref "IC3") (pin "23") (pinfunction "IO15_23") (pintype "bidirectional"))
      (node (ref "R8") (pin "1") (pinfunction "1_1") (pintype "passive"))
      (node (ref "X2") (pin "3") (pinfunction "DI_3") (pintype "bidirectional"))
    )
    (net (code "77") (name "SD_DATA0") (class "Default")
      (node (ref "D2") (pin "A") (pinfunction "A_A") (pintype "passive"))
      (node (ref "IC3") (pin "24") (pinfunction "IO2_24") (pintype "bidirectional"))
      (node (ref "R5") (pin "1") (pinfunction "1_1") (pintype "passive"))
      (node (ref "X2") (pin "7") (pinfunction "DO_7") (pintype "bidirectional"))
    )
    (net (code "78") (name "SD_DATA3") (class "Default")
      (node (ref "IC3") (pin "16") (pinfunction "IO13_16") (pintype "bidirectional"))
      (node (ref "R17") (pin "1") (pinfunction "1_1") (pintype "passive"))
      (node (ref "X2") (pin "2") (pinfunction "CS_2") (pintype "bidirectional"))
    )
    (net (code "79") (name "TEMP") (class "Default")
      (node (ref "IC4") (pin "1") (pinfunction "TEMP_1") (pintype "bidirectional"))
      (node (ref "R32") (pin "1") (pinfunction "1_1") (pintype "passive"))
      (node (ref "X4") (pin "1") (pinfunction "1_1") (pintype "passive"))
    )
    (net (code "80") (name "TSCL") (class "Default")
      (node (ref "X1") (pin "19") (pinfunction "19_19") (pintype "passive"))
    )
    (net (code "81") (name "TSDA") (class "Default")
      (node (ref "X1") (pin "18") (pinfunction "18_18") (pintype "passive"))
    )
    (net (code "82") (name "USB_DN_CON") (class "Default")
      (node (ref "IC1") (pin "5") (pinfunction "D-_5") (pintype "bidirectional"))
      (node (ref "TP137") (pin "P$1") (pinfunction "1_P$1") (pintype "bidirectional"))
      (node (ref "USB1") (pin "2") (pinfunction "2_2") (pintype "input"))
    )
    (net (code "83") (name "USB_DP_CON") (class "Default")
      (node (ref "IC1") (pin "4") (pinfunction "D+_4") (pintype "bidirectional"))
      (node (ref "TP138") (pin "P$1") (pinfunction "1_P$1") (pintype "bidirectional"))
      (node (ref "USB1") (pin "3") (pinfunction "3_3") (pintype "input"))
    )
    (net (code "84") (name "VBAT") (class "Default")
      (node (ref "F2") (pin "2") (pinfunction "2_2") (pintype "bidirectional"))
      (node (ref "R21") (pin "2") (pinfunction "2_2") (pintype "passive"))
      (node (ref "T1") (pin "3") (pinfunction "D_3") (pintype "passive"))
      (node (ref "TP110") (pin "P$1") (pinfunction "1_P$1") (pintype "bidirectional"))
    )
    (net (code "85") (name "VBAT_SENSE") (class "Default")
      (node (ref "C16") (pin "1") (pinfunction "1_1") (pintype "passive"))
      (node (ref "IC3") (pin "7") (pinfunction "IO35_7") (pintype "bidirectional"))
      (node (ref "R20") (pin "2") (pinfunction "2_2") (pintype "passive"))
      (node (ref "R21") (pin "1") (pinfunction "1_1") (pintype "passive"))
    )
    (net (code "86") (name "VCC") (class "Default")
      (node (ref "C14") (pin "1") (pinfunction "1_1") (pintype "passive"))
      (node (ref "C15") (pin "1") (pinfunction "1_1") (pintype "passive"))
      (node (ref "C18") (pin "1") (pinfunction "1_1") (pintype "passive"))
      (node (ref "D3") (pin "C") (pinfunction "C_C") (pintype "passive"))
      (node (ref "IC2") (pin "3") (pinfunction "IN_3") (pintype "input"))
      (node (ref "R2") (pin "2") (pinfunction "2_2") (pintype "passive"))
      (node (ref "R9") (pin "2") (pinfunction "2_2") (pintype "passive"))
      (node (ref "T1") (pin "2") (pinfunction "S_2") (pintype "passive"))
      (node (ref "T2") (pin "2") (pinfunction "S_2") (pintype "passive"))
      (node (ref "TP129") (pin "P$1") (pinfunction "1_P$1") (pintype "bidirectional"))
    )
    (net (code "87") (name "VCOM") (class "Default")
      (node (ref "C38") (pin "2") (pinfunction "2_2") (pintype "passive"))
      (node (ref "X1") (pin "1") (pinfunction "1_1") (pintype "passive"))
    )
    (net (code "88") (name "VDD") (class "Default")
      (node (ref "C8") (pin "1") (pinfunction "1_1") (pintype "passive"))
      (node (ref "IC1") (pin "6") (pinfunction "VDD_6") (pintype "power_in"))
      (node (ref "R12") (pin "2") (pinfunction "2_2") (pintype "passive"))
      (node (ref "R13") (pin "1") (pinfunction "1_1") (pintype "passive"))
      (node (ref "R14") (pin "2") (pinfunction "2_2") (pintype "passive"))
      (node (ref "R3") (pin "2") (pinfunction "2_2") (pintype "passive"))
    )
    (net (code "89") (name "VGH") (class "Default")
      (node (ref "C21") (pin "2") (pinfunction "2_2") (pintype "passive"))
      (node (ref "X1") (pin "20") (pinfunction "20_20") (pintype "passive"))
    )
    (net (code "90") (name "VGL") (class "Default")
      (node (ref "C19") (pin "2") (pinfunction "2_2") (pintype "passive"))
      (node (ref "X1") (pin "21") (pinfunction "21_21") (pintype "passive"))
    )
    (net (code "91") (name "VIBRATOR") (class "Default")
      (node (ref "R11") (pin "2") (pinfunction "2_2") (pintype "passive"))
      (node (ref "U1") (pin "16") (pinfunction "ELE8_16") (pintype "output"))
    )
    (net (code "92") (name "VPP") (class "Default")
      (node (ref "X1") (pin "6") (pinfunction "6_6") (pintype "passive"))
    )
    (net (code "93") (name "VSH") (class "Default")
      (node (ref "C33") (pin "2") (pinfunction "2_2") (pintype "passive"))
      (node (ref "X1") (pin "5") (pinfunction "5_5") (pintype "passive"))
    )
    (net (code "94") (name "VSL") (class "Default")
      (node (ref "C35") (pin "2") (pinfunction "2_2") (pintype "passive"))
      (node (ref "X1") (pin "3") (pinfunction "3_3") (pintype "passive"))
    )
    (net (code "95") (name "VUSB_SENSE") (class "Default")
      (node (ref "C10") (pin "1") (pinfunction "1_1") (pintype "passive"))
      (node (ref "IC3") (pin "6") (pinfunction "IO34_6") (pintype "bidirectional"))
      (node (ref "R6") (pin "2") (pinfunction "2_2") (pintype "passive"))
      (node (ref "R7") (pin "1") (pinfunction "1_1") (pintype "passive"))
    )
    (net (code "96") (name "WS2812_DATA") (class "Default")
      (node (ref "D105") (pin "4") (pinfunction "DIN_4") (pintype "input"))
      (node (ref "IC3") (pin "8") (pinfunction "IO32_8") (pintype "bidirectional"))
      (node (ref "TP136") (pin "P$1") (pinfunction "1_P$1") (pintype "bidirectional"))
    )
    (net (code "97") (name "WS2812_DATA_OUT") (class "Default")
      (node (ref "D100") (pin "2") (pinfunction "DOUT_2") (pintype "output"))
      (node (ref "X3") (pin "8") (pinfunction "5_8") (pintype "passive"))
    )
    (net (code "98") (name "WS2812_POWER") (class "Default")
      (node (ref "C1") (pin "2") (pinfunction "2_2") (pintype "passive"))
      (node (ref "C13") (pin "1") (pinfunction "1_1") (pintype "passive"))
      (node (ref "C2") (pin "2") (pinfunction "2_2") (pintype "passive"))
      (node (ref "C3") (pin "2") (pinfunction "2_2") (pintype "passive"))
      (node (ref "C4") (pin "2") (pinfunction "2_2") (pintype "passive"))
      (node (ref "C5") (pin "2") (pinfunction "2_2") (pintype "passive"))
      (node (ref "C6") (pin "2") (pinfunction "2_2") (pintype "passive"))
      (node (ref "D100") (pin "1") (pinfunction "VDD_1") (pintype "power_in"))
      (node (ref "D101") (pin "1") (pinfunction "VDD_1") (pintype "power_in"))
      (node (ref "D102") (pin "1") (pinfunction "VDD_1") (pintype "power_in"))
      (node (ref "D103") (pin "1") (pinfunction "VDD_1") (pintype "power_in"))
      (node (ref "D104") (pin "1") (pinfunction "VDD_1") (pintype "power_in"))
      (node (ref "D105") (pin "1") (pinfunction "VDD_1") (pintype "power_in"))
      (node (ref "T2") (pin "3") (pinfunction "D_3") (pintype "passive"))
      (node (ref "TP117") (pin "P$1") (pinfunction "1_P$1") (pintype "bidirectional"))
      (node (ref "X3") (pin "2") (pinfunction "11_2") (pintype "passive"))
    )
    (net (code "99") (name "WS2812_POWER_EN") (class "Default")
      (node (ref "R10") (pin "1") (pinfunction "1_1") (pintype "passive"))
      (node (ref "R27") (pin "1") (pinfunction "1_1") (pintype "passive"))
      (node (ref "U1") (pin "18") (pinfunction "ELE10_18") (pintype "output"))
    )
    (net (code "100") (name "unconnected-(IC1-CTS-Pad23)") (class "Default")
      (node (ref "IC1") (pin "23") (pinfunction "CTS_23") (pintype "input"))
    )
    (net (code "101") (name "unconnected-(IC1-DCD-Pad1)") (class "Default")
      (node (ref "IC1") (pin "1") (pinfunction "DCD_1") (pintype "input"))
    )
    (net (code "102") (name "unconnected-(IC1-DSR-Pad27)") (class "Default")
      (node (ref "IC1") (pin "27") (pinfunction "DSR_27") (pintype "input"))
    )
    (net (code "103") (name "unconnected-(IC1-RI-Pad2)") (class "Default")
      (node (ref "IC1") (pin "2") (pinfunction "RI_2") (pintype "input"))
    )
    (net (code "104") (name "unconnected-(IC1-SUSPEND-Pad12)") (class "Default")
      (node (ref "IC1") (pin "12") (pinfunction "SUSPEND_12") (pintype "output"))
    )
    (net (code "105") (name "unconnected-(IC1-~{SUSPEND}-Pad11)") (class "Default")
      (node (ref "IC1") (pin "11") (pinfunction "~{SUSPEND}_11") (pintype "output"))
    )
    (net (code "106") (name "unconnected-(IC3-IO20-Pad32)") (class "Default")
      (node (ref "IC3") (pin "32") (pinfunction "IO20_32") (pintype "bidirectional"))
    )
    (net (code "107") (name "unconnected-(IC4-STDBY-Pad6)") (class "Default")
      (node (ref "IC4") (pin "6") (pinfunction "STDBY_6") (pintype "bidirectional"))
    )
    (net (code "108") (name "unconnected-(USB1-Pad4)") (class "Default")
      (node (ref "USB1") (pin "4") (pinfunction "4_4") (pintype "input"))
    )
    (net (code "109") (name "unconnected-(X1-Pad24)") (class "Default")
      (node (ref "X1") (pin "24") (pinfunction "24_24") (pintype "passive"))
    )
    (net (code "110") (name "unconnected-(X2-NC-Pad1)") (class "Default")
      (node (ref "X2") (pin "1") (pinfunction "NC_1") (pintype "bidirectional"))
    )
    (net (code "111") (name "unconnected-(X2-RSV-Pad8)") (class "Default")
      (node (ref "X2") (pin "8") (pinfunction "RSV_8") (pintype "bidirectional"))
    )
  )
)
